# 03_-_28_PINS_SCHEMATIC.net
KiCad netlist of a schematic drawn in Altium Designer
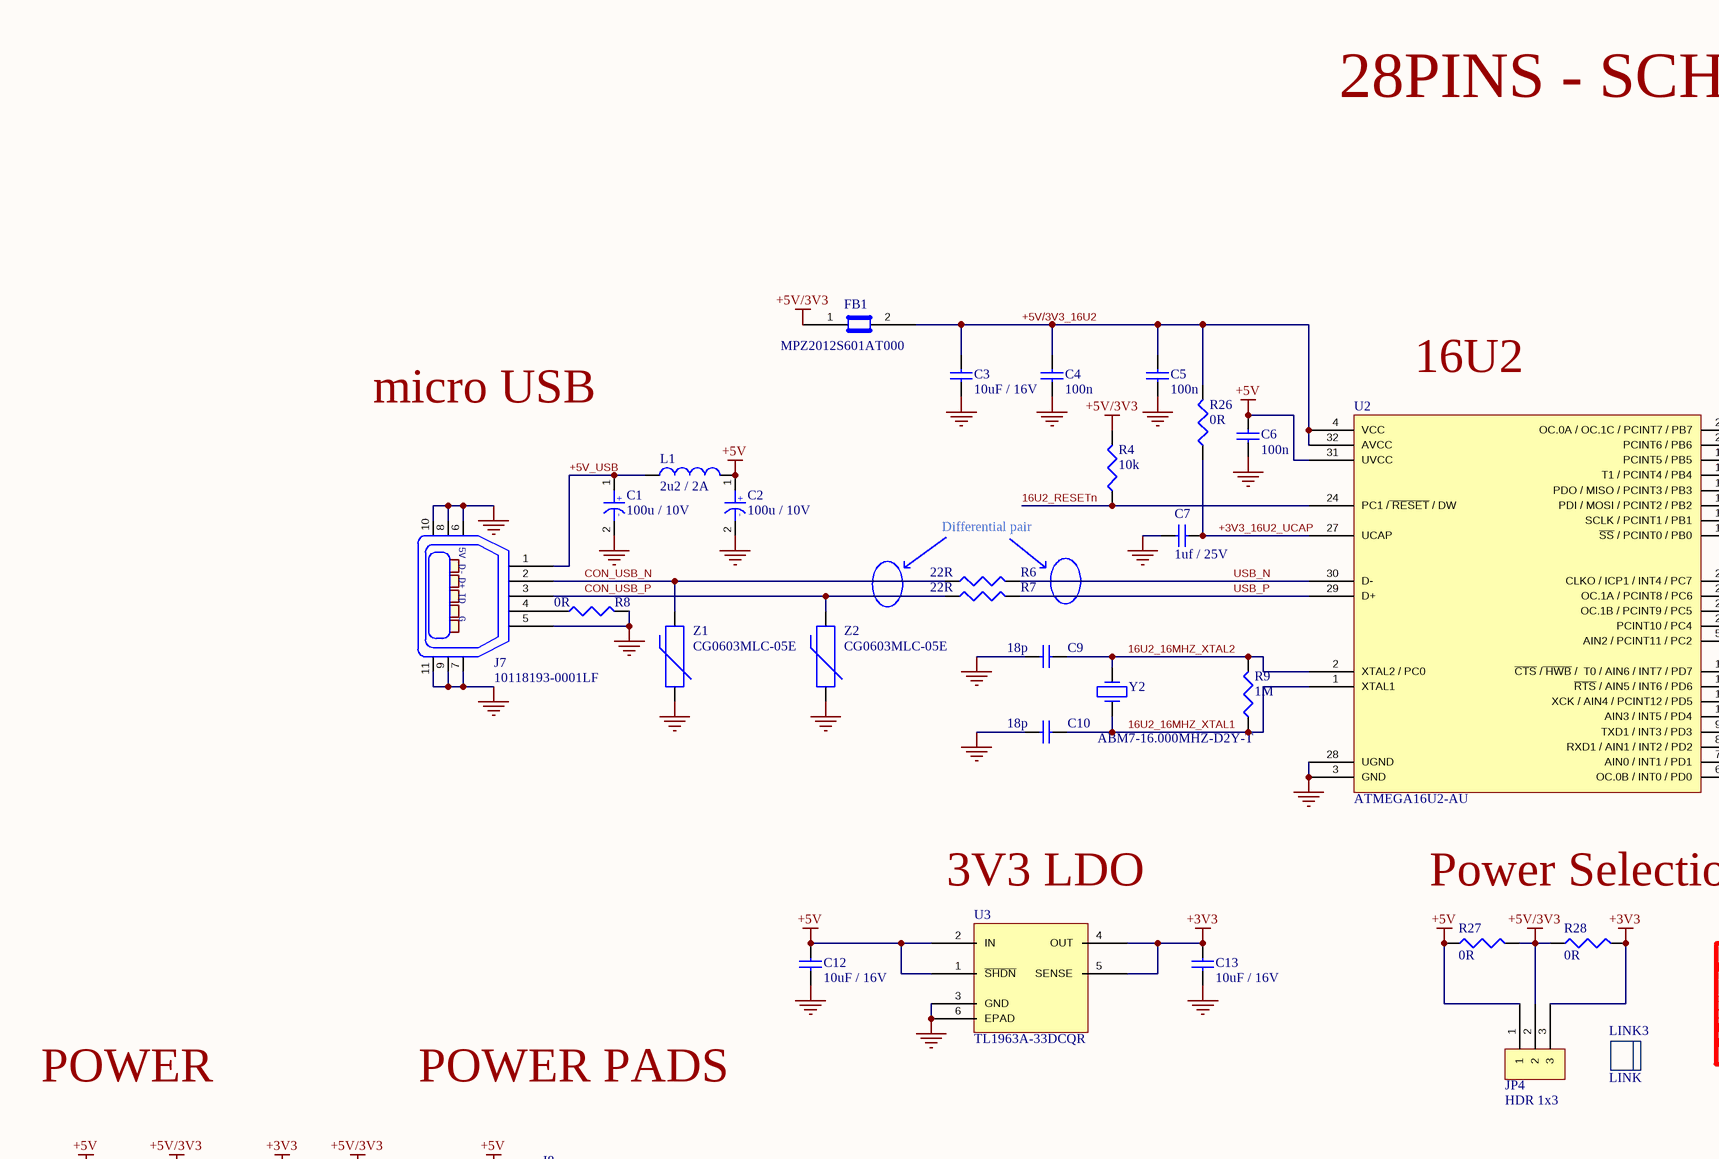
[diagram p0: [03] - 28 PINS SCHEMATIC.SchDoc, top left]
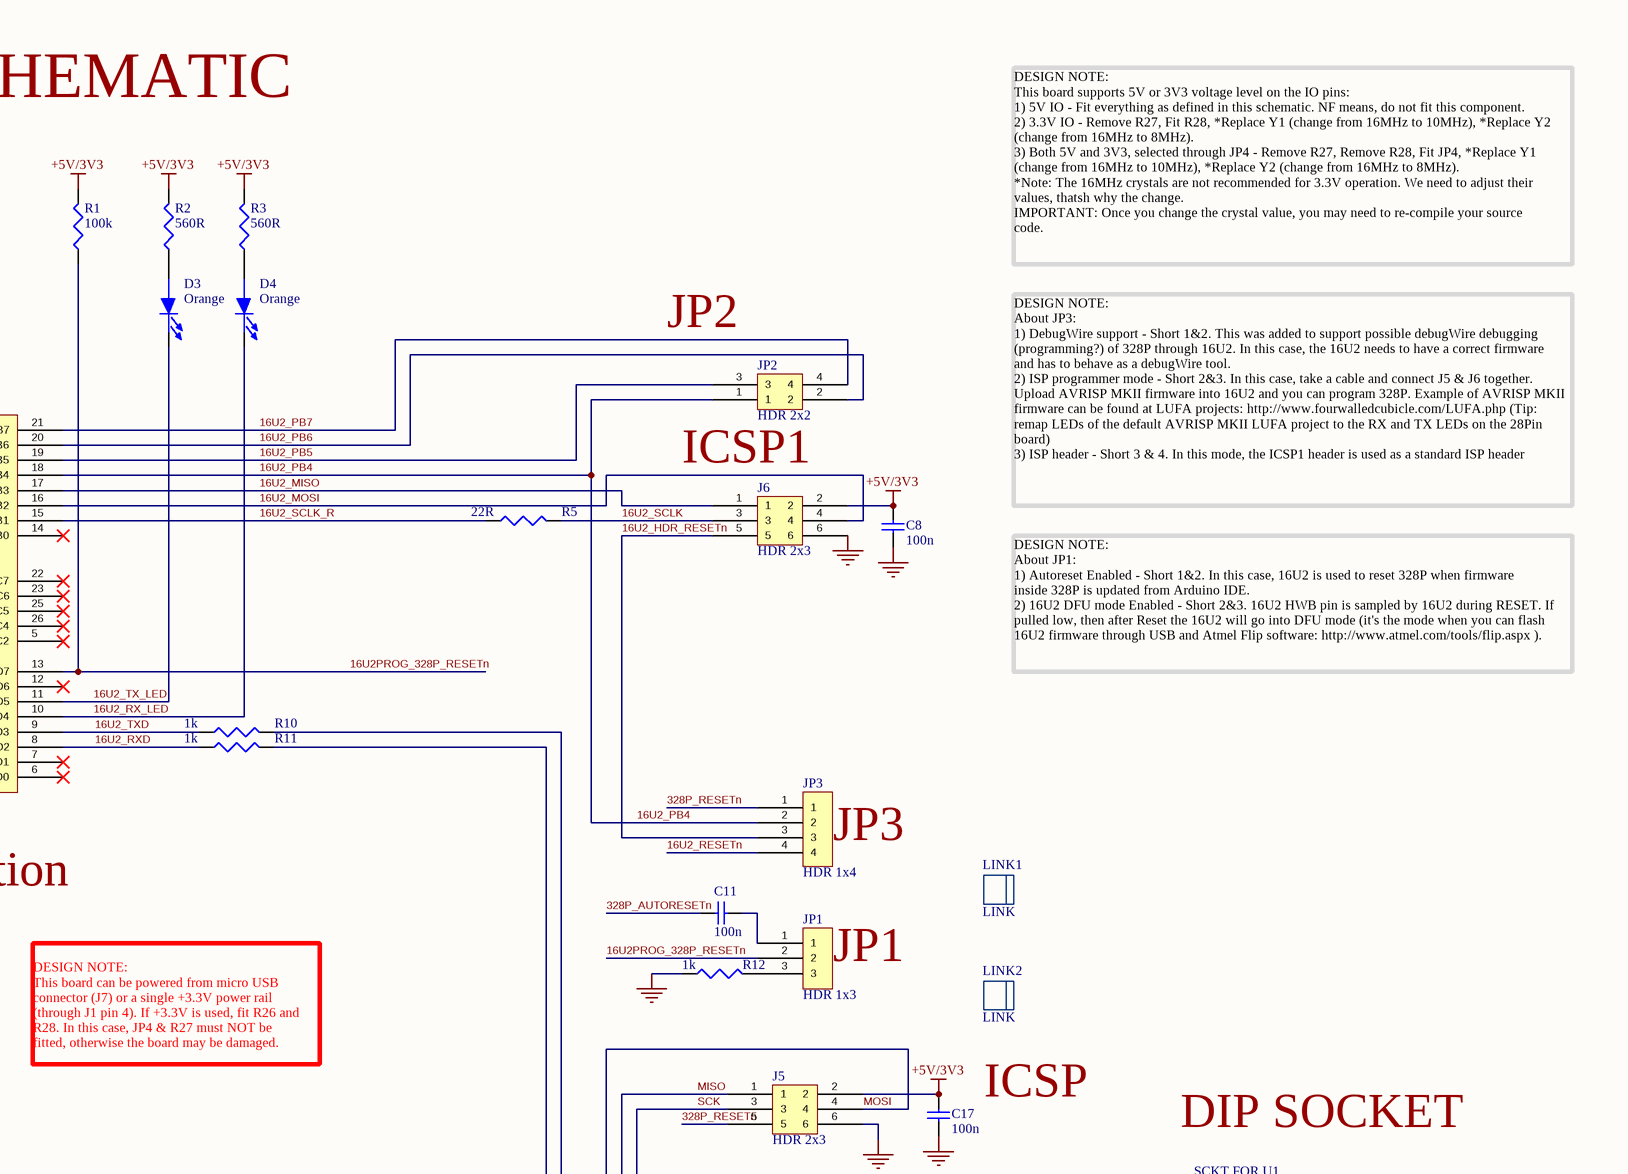
[diagram p1: [03] - 28 PINS SCHEMATIC.SchDoc, top right]
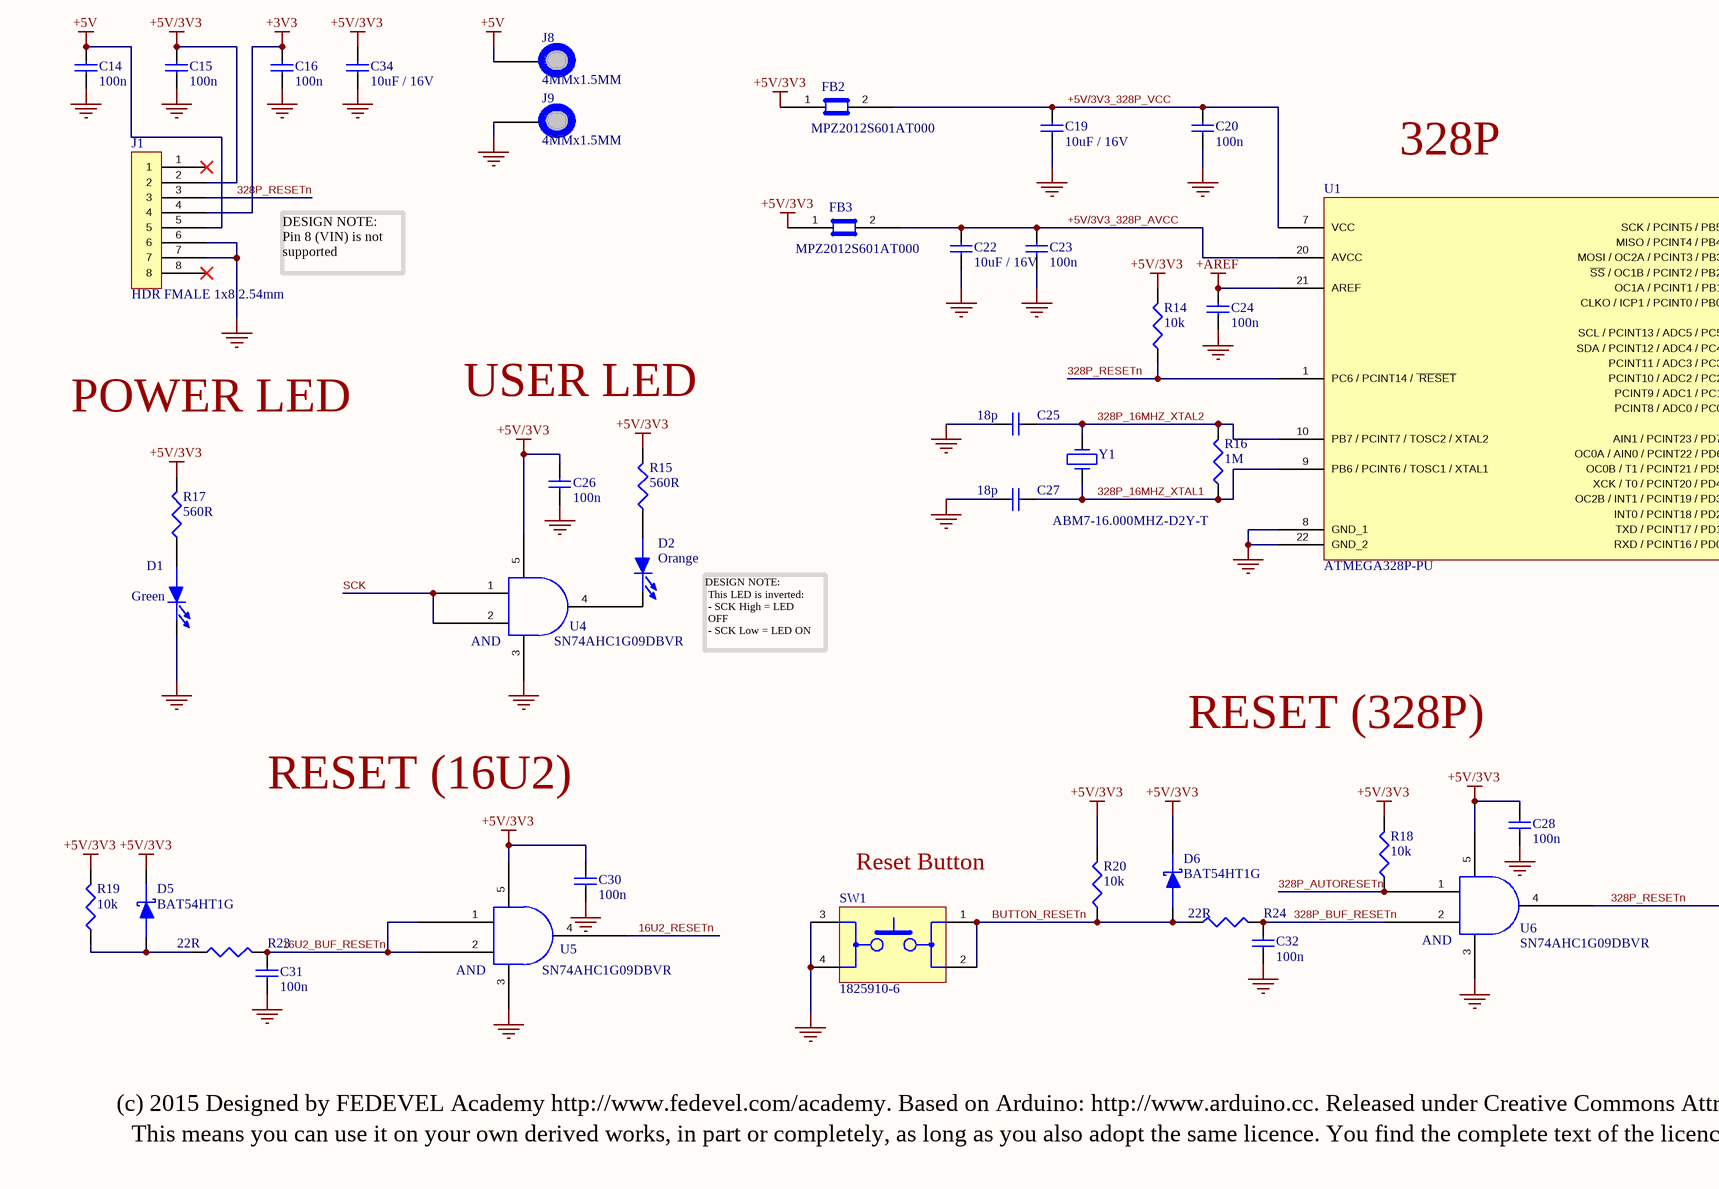
[diagram p2: [03] - 28 PINS SCHEMATIC.SchDoc, bottom left]
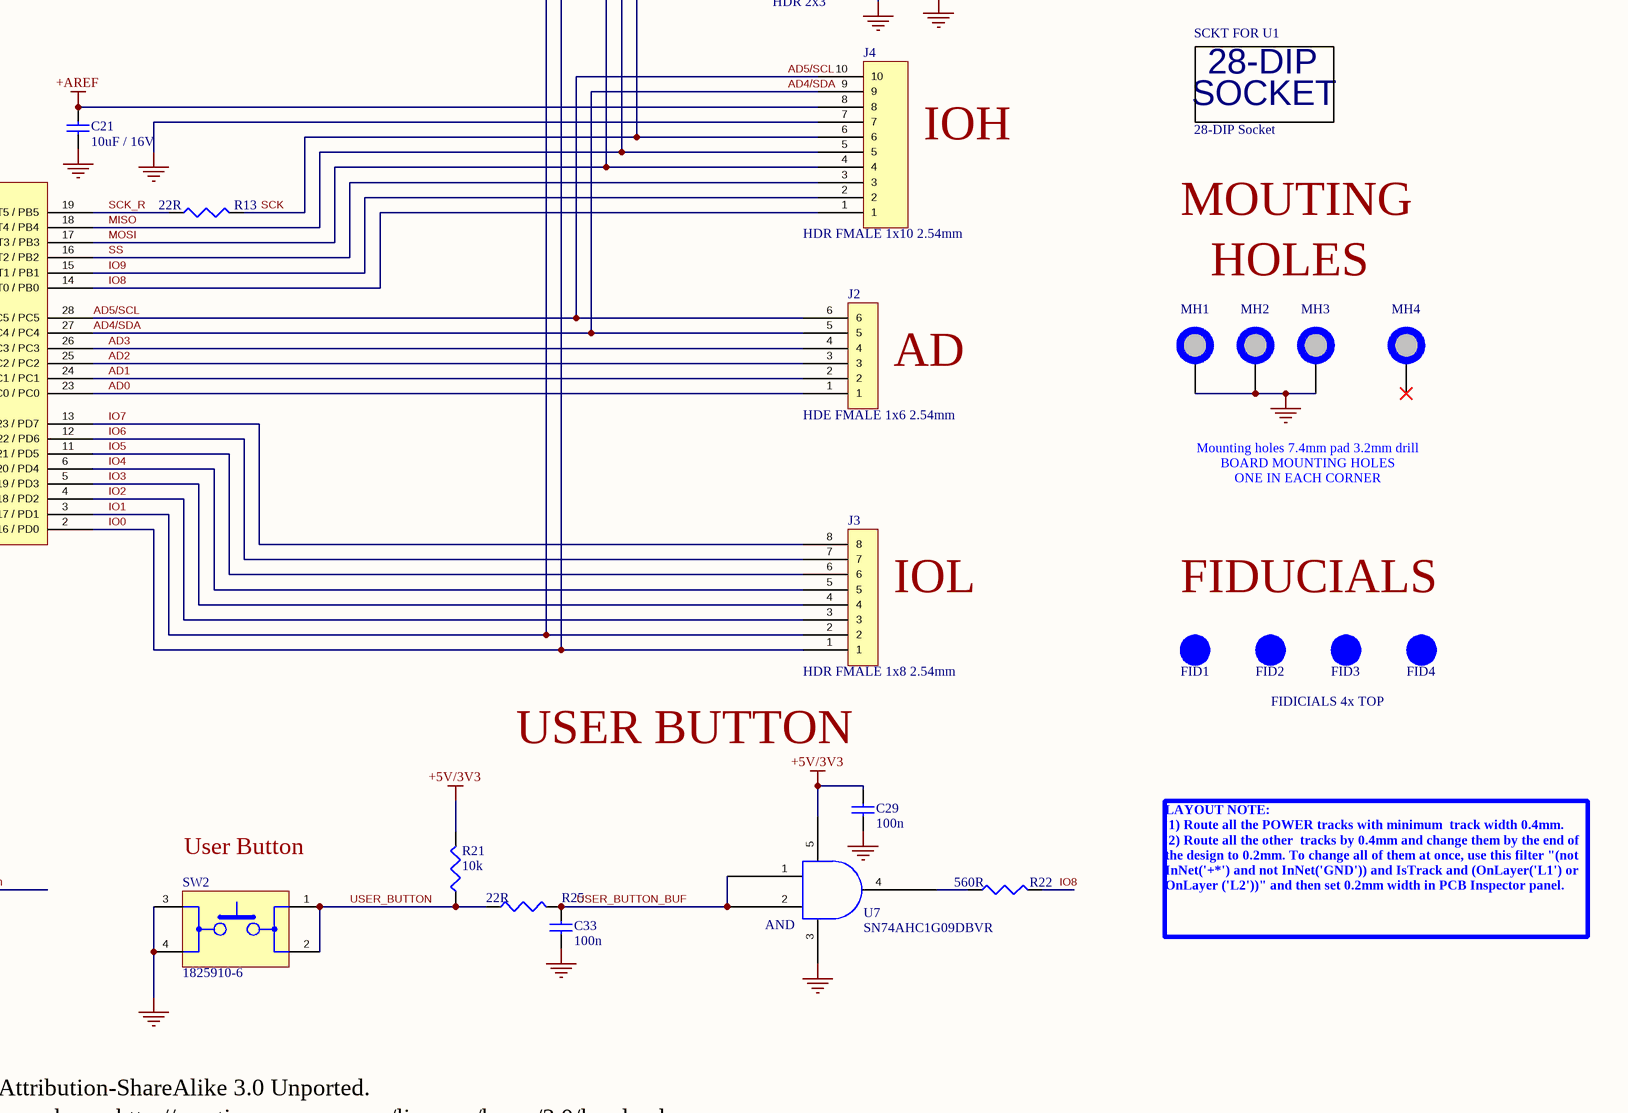
[diagram p3: [03] - 28 PINS SCHEMATIC.SchDoc, bottom right]

(export (version "E")
  (design (tool "Eeschema 10.0.6"))
  (components
    (comp (ref "C1")
      (value "100u / 10V")
      (footprint "C_ALU_C_SIZE")
      (description "Cap Aluminum Lytic 100uF 10V 20% (5 X 5.4mm) SMD 50mA 1000h 85C Automotive T/R")
      (fields
        (field (name "MANUFACTURER") "Panasonic")
        (field (name "MANUFACTURER PART NUMBER") "EEE-1AA101WR")
      )
      (libsource (lib "28Pins_Project_V1I1") (part "EEE-1AA101WR"))
    )
    (comp (ref "C2")
      (value "100u / 10V")
      (footprint "C_ALU_C_SIZE")
      (description "Cap Aluminum Lytic 100uF 10V 20% (5 X 5.4mm) SMD 50mA 1000h 85C Automotive T/R")
      (fields
        (field (name "MANUFACTURER") "Panasonic")
        (field (name "MANUFACTURER PART NUMBER") "EEE-1AA101WR")
      )
      (libsource (lib "28Pins_Project_V1I1") (part "EEE-1AA101WR"))
    )
    (comp (ref "C3")
      (value "10uF / 16V")
      (footprint "C0805 - 10uf")
      (description "CAP CER 10UF 16V X5R 0805")
      (fields
        (field (name "MANUFACTURER") "TDK")
        (field (name "MANUFACTURER PART NUMBER") "C2012X5R1C106M125AC")
      )
      (libsource (lib "28Pins_Project_V1I1") (part "C2012X5R1C106M125AC"))
    )
    (comp (ref "C4")
      (value "100n")
      (footprint "C0805")
      (description "CAP CER 0.1UF 50V X7R 0805")
      (fields
        (field (name "MANUFACTURER") "TDK")
        (field (name "MANUFACTURER PART NUMBER") "C2012X7R1H104K085AA")
      )
      (libsource (lib "28Pins_Project_V1I1") (part "C2012X7R1H104K085AA"))
    )
    (comp (ref "C5")
      (value "100n")
      (footprint "C0805")
      (description "CAP CER 0.1UF 50V X7R 0805")
      (fields
        (field (name "MANUFACTURER") "TDK")
        (field (name "MANUFACTURER PART NUMBER") "C2012X7R1H104K085AA")
      )
      (libsource (lib "28Pins_Project_V1I1") (part "C2012X7R1H104K085AA"))
    )
    (comp (ref "C6")
      (value "100n")
      (footprint "C0805")
      (description "CAP CER 0.1UF 50V X7R 0805")
      (fields
        (field (name "MANUFACTURER") "TDK")
        (field (name "MANUFACTURER PART NUMBER") "C2012X7R1H104K085AA")
      )
      (libsource (lib "28Pins_Project_V1I1") (part "C2012X7R1H104K085AA"))
    )
    (comp (ref "C7")
      (value "1uf / 25V")
      (footprint "C0805")
      (description "CAP CER 1UF 25V X5R 0805")
      (fields
        (field (name "MANUFACTURER") "TDK")
        (field (name "MANUFACTURER PART NUMBER") "C2012X5R1E105K125AA")
      )
      (libsource (lib "28Pins_Project_V1I1") (part "C2012X5R1E105K125AA"))
    )
    (comp (ref "C8")
      (value "100n")
      (footprint "C0805")
      (description "CAP CER 0.1UF 50V X7R 0805")
      (fields
        (field (name "MANUFACTURER") "TDK")
        (field (name "MANUFACTURER PART NUMBER") "C2012X7R1H104K085AA")
      )
      (libsource (lib "28Pins_Project_V1I1") (part "C2012X7R1H104K085AA"))
    )
    (comp (ref "C9")
      (value "18p")
      (footprint "C0805")
      (description "CAP CER 18PF 50V NP0 0805")
      (fields
        (field (name "MANUFACTURER") "KEMET")
        (field (name "MANUFACTURER PART NUMBER") "C0805C180J5GAC-TU")
      )
      (libsource (lib "28Pins_Project_V1I1") (part "C0805C180J5GAC-TU"))
    )
    (comp (ref "C10")
      (value "18p")
      (footprint "C0805")
      (description "CAP CER 18PF 50V NP0 0805")
      (fields
        (field (name "MANUFACTURER") "KEMET")
        (field (name "MANUFACTURER PART NUMBER") "C0805C180J5GAC-TU")
      )
      (libsource (lib "28Pins_Project_V1I1") (part "C0805C180J5GAC-TU"))
    )
    (comp (ref "C11")
      (value "100n")
      (footprint "C0805")
      (description "CAP CER 0.1UF 50V X7R 0805")
      (fields
        (field (name "MANUFACTURER") "TDK")
        (field (name "MANUFACTURER PART NUMBER") "C2012X7R1H104K085AA")
      )
      (libsource (lib "28Pins_Project_V1I1") (part "C2012X7R1H104K085AA"))
    )
    (comp (ref "C12")
      (value "10uF / 16V")
      (footprint "C0805 - 10uf")
      (description "CAP CER 10UF 16V X5R 0805")
      (fields
        (field (name "MANUFACTURER") "TDK")
        (field (name "MANUFACTURER PART NUMBER") "C2012X5R1C106M125AC")
      )
      (libsource (lib "28Pins_Project_V1I1") (part "C2012X5R1C106M125AC"))
    )
    (comp (ref "C13")
      (value "10uF / 16V")
      (footprint "C0805 - 10uf")
      (description "CAP CER 10UF 16V X5R 0805")
      (fields
        (field (name "MANUFACTURER") "TDK")
        (field (name "MANUFACTURER PART NUMBER") "C2012X5R1C106M125AC")
      )
      (libsource (lib "28Pins_Project_V1I1") (part "C2012X5R1C106M125AC"))
    )
    (comp (ref "C14")
      (value "100n")
      (footprint "C0805")
      (description "CAP CER 0.1UF 50V X7R 0805")
      (fields
        (field (name "MANUFACTURER") "TDK")
        (field (name "MANUFACTURER PART NUMBER") "C2012X7R1H104K085AA")
      )
      (libsource (lib "28Pins_Project_V1I1") (part "C2012X7R1H104K085AA"))
    )
    (comp (ref "C15")
      (value "100n")
      (footprint "C0805")
      (description "CAP CER 0.1UF 50V X7R 0805")
      (fields
        (field (name "MANUFACTURER") "TDK")
        (field (name "MANUFACTURER PART NUMBER") "C2012X7R1H104K085AA")
      )
      (libsource (lib "28Pins_Project_V1I1") (part "C2012X7R1H104K085AA"))
    )
    (comp (ref "C16")
      (value "100n")
      (footprint "C0805")
      (description "CAP CER 0.1UF 50V X7R 0805")
      (fields
        (field (name "MANUFACTURER") "TDK")
        (field (name "MANUFACTURER PART NUMBER") "C2012X7R1H104K085AA")
      )
      (libsource (lib "28Pins_Project_V1I1") (part "C2012X7R1H104K085AA"))
    )
    (comp (ref "C17")
      (value "100n")
      (footprint "C0805")
      (description "CAP CER 0.1UF 50V X7R 0805")
      (fields
        (field (name "MANUFACTURER") "TDK")
        (field (name "MANUFACTURER PART NUMBER") "C2012X7R1H104K085AA")
      )
      (libsource (lib "28Pins_Project_V1I1") (part "C2012X7R1H104K085AA"))
    )
    (comp (ref "C19")
      (value "10uF / 16V")
      (footprint "C0805 - 10uf")
      (description "CAP CER 10UF 16V X5R 0805")
      (fields
        (field (name "MANUFACTURER") "TDK")
        (field (name "MANUFACTURER PART NUMBER") "C2012X5R1C106M125AC")
      )
      (libsource (lib "28Pins_Project_V1I1") (part "C2012X5R1C106M125AC"))
    )
    (comp (ref "C20")
      (value "100n")
      (footprint "C0805")
      (description "CAP CER 0.1UF 50V X7R 0805")
      (fields
        (field (name "MANUFACTURER") "TDK")
        (field (name "MANUFACTURER PART NUMBER") "C2012X7R1H104K085AA")
      )
      (libsource (lib "28Pins_Project_V1I1") (part "C2012X7R1H104K085AA"))
    )
    (comp (ref "C21")
      (value "10uF / 16V")
      (footprint "C0805 - 10uf")
      (description "CAP CER 10UF 16V X5R 0805")
      (fields
        (field (name "MANUFACTURER") "TDK")
        (field (name "MANUFACTURER PART NUMBER") "C2012X5R1C106M125AC")
      )
      (libsource (lib "28Pins_Project_V1I1") (part "C2012X5R1C106M125AC"))
    )
    (comp (ref "C22")
      (value "10uF / 16V")
      (footprint "C0805 - 10uf")
      (description "CAP CER 10UF 16V X5R 0805")
      (fields
        (field (name "MANUFACTURER") "TDK")
        (field (name "MANUFACTURER PART NUMBER") "C2012X5R1C106M125AC")
      )
      (libsource (lib "28Pins_Project_V1I1") (part "C2012X5R1C106M125AC"))
    )
    (comp (ref "C23")
      (value "100n")
      (footprint "C0805")
      (description "CAP CER 0.1UF 50V X7R 0805")
      (fields
        (field (name "MANUFACTURER") "TDK")
        (field (name "MANUFACTURER PART NUMBER") "C2012X7R1H104K085AA")
      )
      (libsource (lib "28Pins_Project_V1I1") (part "C2012X7R1H104K085AA"))
    )
    (comp (ref "C24")
      (value "100n")
      (footprint "C0805")
      (description "CAP CER 0.1UF 50V X7R 0805")
      (fields
        (field (name "MANUFACTURER") "TDK")
        (field (name "MANUFACTURER PART NUMBER") "C2012X7R1H104K085AA")
      )
      (libsource (lib "28Pins_Project_V1I1") (part "C2012X7R1H104K085AA"))
    )
    (comp (ref "C25")
      (value "18p")
      (footprint "C0805")
      (description "CAP CER 18PF 50V NP0 0805")
      (fields
        (field (name "MANUFACTURER") "KEMET")
        (field (name "MANUFACTURER PART NUMBER") "C0805C180J5GAC-TU")
      )
      (libsource (lib "28Pins_Project_V1I1") (part "C0805C180J5GAC-TU"))
    )
    (comp (ref "C26")
      (value "100n")
      (footprint "C0805")
      (description "CAP CER 0.1UF 50V X7R 0805")
      (fields
        (field (name "MANUFACTURER") "TDK")
        (field (name "MANUFACTURER PART NUMBER") "C2012X7R1H104K085AA")
      )
      (libsource (lib "28Pins_Project_V1I1") (part "C2012X7R1H104K085AA"))
    )
    (comp (ref "C27")
      (value "18p")
      (footprint "C0805")
      (description "CAP CER 18PF 50V NP0 0805")
      (fields
        (field (name "MANUFACTURER") "KEMET")
        (field (name "MANUFACTURER PART NUMBER") "C0805C180J5GAC-TU")
      )
      (libsource (lib "28Pins_Project_V1I1") (part "C0805C180J5GAC-TU"))
    )
    (comp (ref "C28")
      (value "100n")
      (footprint "C0805")
      (description "CAP CER 0.1UF 50V X7R 0805")
      (fields
        (field (name "MANUFACTURER") "TDK")
        (field (name "MANUFACTURER PART NUMBER") "C2012X7R1H104K085AA")
      )
      (libsource (lib "28Pins_Project_V1I1") (part "C2012X7R1H104K085AA"))
    )
    (comp (ref "C29")
      (value "100n")
      (footprint "C0805")
      (description "CAP CER 0.1UF 50V X7R 0805")
      (fields
        (field (name "MANUFACTURER") "TDK")
        (field (name "MANUFACTURER PART NUMBER") "C2012X7R1H104K085AA")
      )
      (libsource (lib "28Pins_Project_V1I1") (part "C2012X7R1H104K085AA"))
    )
    (comp (ref "C30")
      (value "100n")
      (footprint "C0805")
      (description "CAP CER 0.1UF 50V X7R 0805")
      (fields
        (field (name "MANUFACTURER") "TDK")
        (field (name "MANUFACTURER PART NUMBER") "C2012X7R1H104K085AA")
      )
      (libsource (lib "28Pins_Project_V1I1") (part "C2012X7R1H104K085AA"))
    )
    (comp (ref "C31")
      (value "100n")
      (footprint "C0805")
      (description "CAP CER 0.1UF 50V X7R 0805")
      (fields
        (field (name "MANUFACTURER") "TDK")
        (field (name "MANUFACTURER PART NUMBER") "C2012X7R1H104K085AA")
      )
      (libsource (lib "28Pins_Project_V1I1") (part "C2012X7R1H104K085AA"))
    )
    (comp (ref "C32")
      (value "100n")
      (footprint "C0805")
      (description "CAP CER 0.1UF 50V X7R 0805")
      (fields
        (field (name "MANUFACTURER") "TDK")
        (field (name "MANUFACTURER PART NUMBER") "C2012X7R1H104K085AA")
      )
      (libsource (lib "28Pins_Project_V1I1") (part "C2012X7R1H104K085AA"))
    )
    (comp (ref "C33")
      (value "100n")
      (footprint "C0805")
      (description "CAP CER 0.1UF 50V X7R 0805")
      (fields
        (field (name "MANUFACTURER") "TDK")
        (field (name "MANUFACTURER PART NUMBER") "C2012X7R1H104K085AA")
      )
      (libsource (lib "28Pins_Project_V1I1") (part "C2012X7R1H104K085AA"))
    )
    (comp (ref "C34")
      (value "10uF / 16V")
      (footprint "C0805 - 10uf")
      (description "CAP CER 10UF 16V X5R 0805")
      (fields
        (field (name "MANUFACTURER") "TDK")
        (field (name "MANUFACTURER PART NUMBER") "C2012X5R1C106M125AC")
      )
      (libsource (lib "28Pins_Project_V1I1") (part "C2012X5R1C106M125AC"))
    )
    (comp (ref "D1")
      (value "Green")
      (footprint "LED_0603")
      (description "LED GREEN DIFFUSED 0603 SMD")
      (fields
        (field (name "MANUFACTURER") "Osram Opto")
        (field (name "MANUFACTURER PART NUMBER") "LGL29K-G2J1-24-Z")
      )
      (libsource (lib "28Pins_Project_V1I1") (part "LGL29K-G2J1-24-Z"))
    )
    (comp (ref "D2")
      (value "Orange")
      (footprint "LED_0603")
      (description "LED ORANGE DIFFUSED 0603 SMD")
      (fields
        (field (name "MANUFACTURER") "Osram Opto")
        (field (name "MANUFACTURER PART NUMBER") "LOL29K-H2K1-24-Z")
      )
      (libsource (lib "28Pins_Project_V1I1") (part "LOL29K-H2K1-24-Z"))
    )
    (comp (ref "D3")
      (value "Orange")
      (footprint "LED_0603")
      (description "LED ORANGE DIFFUSED 0603 SMD")
      (fields
        (field (name "MANUFACTURER") "Osram Opto")
        (field (name "MANUFACTURER PART NUMBER") "LOL29K-H2K1-24-Z")
      )
      (libsource (lib "28Pins_Project_V1I1") (part "LOL29K-H2K1-24-Z"))
    )
    (comp (ref "D4")
      (value "Orange")
      (footprint "LED_0603")
      (description "LED ORANGE DIFFUSED 0603 SMD")
      (fields
        (field (name "MANUFACTURER") "Osram Opto")
        (field (name "MANUFACTURER PART NUMBER") "LOL29K-H2K1-24-Z")
      )
      (libsource (lib "28Pins_Project_V1I1") (part "LOL29K-H2K1-24-Z"))
    )
    (comp (ref "D5")
      (value "BAT54HT1G")
      (footprint "SOD323")
      (description "DIODE SCHOTTKY 30V 200MA SOD323")
      (fields (field (name "MANUFACTURER") "ON Semiconductor / Fairchild"))
      (libsource (lib "28Pins_Project_V1I1") (part "BAT54HT1G"))
    )
    (comp (ref "D6")
      (value "BAT54HT1G")
      (footprint "SOD323")
      (description "DIODE SCHOTTKY 30V 200MA SOD323")
      (fields (field (name "MANUFACTURER") "ON Semiconductor / Fairchild"))
      (libsource (lib "28Pins_Project_V1I1") (part "BAT54HT1G"))
    )
    (comp (ref "FB1")
      (value "MPZ2012S601AT000")
      (footprint "C0805")
      (description "TDK   MPZ2012S601AT000   FERRITE BEAD, 0.1OHM, 2A, 0805, FULL REEL")
      (fields (field (name "MANUFACTURER") "TDK"))
      (libsource (lib "28Pins_Project_V1I1") (part "MPZ2012S601AT000"))
    )
    (comp (ref "FB2")
      (value "MPZ2012S601AT000")
      (footprint "C0805")
      (description "TDK   MPZ2012S601AT000   FERRITE BEAD, 0.1OHM, 2A, 0805, FULL REEL")
      (fields (field (name "MANUFACTURER") "TDK"))
      (libsource (lib "28Pins_Project_V1I1") (part "MPZ2012S601AT000"))
    )
    (comp (ref "FB3")
      (value "MPZ2012S601AT000")
      (footprint "C0805")
      (description "TDK   MPZ2012S601AT000   FERRITE BEAD, 0.1OHM, 2A, 0805, FULL REEL")
      (fields (field (name "MANUFACTURER") "TDK"))
      (libsource (lib "28Pins_Project_V1I1") (part "MPZ2012S601AT000"))
    )
    (comp (ref "FID1")
      (value "FID_1MMC")
      (footprint "FID_40x120D")
      (description "Fiducial 40mil Diameter, 20mil Mask")
      (libsource (lib "28Pins_Project_V1I1") (part "FID_1MMC"))
    )
    (comp (ref "FID2")
      (value "FID_1MMC")
      (footprint "FID_40x120D")
      (description "Fiducial 40mil Diameter, 20mil Mask")
      (libsource (lib "28Pins_Project_V1I1") (part "FID_1MMC"))
    )
    (comp (ref "FID3")
      (value "FID_1MMC")
      (footprint "FID_40x120D")
      (description "Fiducial 40mil Diameter, 20mil Mask")
      (libsource (lib "28Pins_Project_V1I1") (part "FID_1MMC"))
    )
    (comp (ref "FID4")
      (value "FID_1MMC")
      (footprint "FID_40x120D")
      (description "Fiducial 40mil Diameter, 20mil Mask")
      (libsource (lib "28Pins_Project_V1I1") (part "FID_1MMC"))
    )
    (comp (ref "J1")
      (value "HDR FMALE 1x8 2.54mm")
      (footprint "HDR FMALE 1x8 2.54mm")
      (description "Headers & Wire Housings 8 PIN SIL VERTICAL SOCKET GOLD+TIN")
      (fields (field (name "MANUFACTURER") "Harwin") (field (name "MANUFACTURER PART NUMBER") "M20-7820842"))
      (libsource (lib "") (part "M20-7820842_1"))
    )
    (comp (ref "J2")
      (value "HDE FMALE 1x6 2.54mm")
      (footprint "HDR FMALE 1x6 2.54mm")
      (description "Headers & Wire Housings 6 PIN SIL VERTICAL SOCKET TIN")
      (fields (field (name "MANUFACTURER") "Harwin") (field (name "MANUFACTURER PART NUMBER") "M20-7820646"))
      (libsource (lib "28Pins_Project_V1I1") (part "M20-7820646"))
    )
    (comp (ref "J3")
      (value "HDR FMALE 1x8 2.54mm")
      (footprint "HDR FMALE 1x8 2.54mm")
      (description "Headers & Wire Housings 8 PIN SIL VERTICAL SOCKET GOLD+TIN")
      (fields (field (name "MANUFACTURER") "Harwin") (field (name "MANUFACTURER PART NUMBER") "M20-7820842"))
      (libsource (lib "28Pins_Project_V1I1") (part "M20-7820842"))
    )
    (comp (ref "J4")
      (value "HDR FMALE 1x10 2.54mm")
      (footprint "HDR FMALE 1x10 2.54mm")
      (description "Headers & Wire Housings 10 PIN SIL VERTICAL SOCKET TIN")
      (fields (field (name "MANUFACTURER") "Harwin") (field (name "MANUFACTURER PART NUMBER") "M20-7821046"))
      (libsource (lib "28Pins_Project_V1I1") (part "M20-7821046"))
    )
    (comp (ref "J5")
      (value "HDR 2x3")
      (footprint "HDR_2x3_2.54mm")
      (description "6 Positions Header, Unshrouded Connector 0.100\" (2.54mm) Through Hole Gold or Gold, GXT™")
      (fields
        (field (name "MANUFACTURER") "Amphenol FCI")
        (field (name "MANUFACTURER PART NUMBER") "67997-106HLF")
      )
      (libsource (lib "28Pins_Project_V1I1") (part "67997-106HLF"))
    )
    (comp (ref "J6")
      (value "HDR 2x3")
      (footprint "HDR_2x3_2.54mm")
      (description "6 Positions Header, Unshrouded Connector 0.100\" (2.54mm) Through Hole Gold or Gold, GXT™")
      (fields
        (field (name "MANUFACTURER") "Amphenol FCI")
        (field (name "MANUFACTURER PART NUMBER") "67997-106HLF")
      )
      (libsource (lib "28Pins_Project_V1I1") (part "67997-106HLF"))
    )
    (comp (ref "J7")
      (value "10118193-0001LF")
      (footprint "10118193")
      (description "USB - micro B USB 2.0 Receptacle Connector 5 Position Surface Mount, Right Angle, Horizontal")
      (fields (field (name "MANUFACTURER") "Amphenol FCI"))
      (libsource (lib "28Pins_Project_V1I1") (part "10118193-0001LF"))
    )
    (comp (ref "J8")
      (value "4MMx1.5MM")
      (footprint "PAD_WITH_HOLE_4MMx1.5MM")
      (description "Pad with a hole 4mmx1.5mm")
      (libsource (lib "28Pins_Project_V1I1") (part "PAD_WITH_HOLE_4MMx1.5MM"))
    )
    (comp (ref "J9")
      (value "4MMx1.5MM")
      (footprint "PAD_WITH_HOLE_4MMx1.5MM")
      (description "Pad with a hole 4mmx1.5mm")
      (libsource (lib "28Pins_Project_V1I1") (part "PAD_WITH_HOLE_4MMx1.5MM"))
    )
    (comp (ref "JP1")
      (value "HDR 1x3")
      (footprint "HDR FMALE 1x3 2.54mm")
      (description "3 Positions Header, Unshrouded Connector 0.100\" (2.54mm) Through Hole Gold or Gold, GXT™")
      (fields
        (field (name "MANUFACTURER") "Amphenol FCI")
        (field (name "MANUFACTURER PART NUMBER") "68000-103HLF")
      )
      (libsource (lib "") (part "68000-103HLF_1"))
    )
    (comp (ref "JP2")
      (value "HDR 2x2")
      (footprint "HDR_2x2_2.54mm")
      (description "4 Positions Header, Unshrouded Connector 0.100\" (2.54mm) Through Hole Gold or Gold, GXT™")
      (fields
        (field (name "MANUFACTURER") "Amphenol FCI")
        (field (name "MANUFACTURER PART NUMBER") "68602-204HLF")
      )
      (libsource (lib "28Pins_Project_V1I1") (part "68602-204HLF"))
    )
    (comp (ref "JP3")
      (value "HDR 1x4")
      (footprint "HDR _1x4_2.54mm")
      (description "4 Positions Header, Unshrouded Connector 0.100\" (2.54mm) Through Hole Gold or Gold, GXT™")
      (fields
        (field (name "MANUFACTURER") "Amphenol FCI")
        (field (name "MANUFACTURER PART NUMBER") "68001-204HLF")
      )
      (libsource (lib "28Pins_Project_V1I1") (part "68001-204HLF"))
    )
    (comp (ref "JP4")
      (value "HDR 1x3")
      (footprint "HDR FMALE 1x3 2.54mm")
      (description "3 Positions Header, Unshrouded Connector 0.100\" (2.54mm) Through Hole Gold or Gold, GXT™")
      (fields
        (field (name "MANUFACTURER") "Amphenol FCI")
        (field (name "MANUFACTURER PART NUMBER") "68000-103HLF")
      )
      (libsource (lib "28Pins_Project_V1I1") (part "68000-103HLF"))
    )
    (comp (ref "L1")
      (value "2u2 / 2A")
      (footprint "C1210_IND")
      (description "Inductor Chip Wirewound 2.2uH 20% 100KHz 1.13A 80mOhm DCR 1210 T/R")
      (fields
        (field (name "MANUFACTURER") "KEMET")
        (field (name "MANUFACTURER PART NUMBER") "L1210R2R2MDWIT")
      )
      (libsource (lib "28Pins_Project_V1I1") (part "L1210R2R2MDWIT"))
    )
    (comp (ref "LINK1")
      (value "LINK")
      (description "CONN JUMPER SHORTING .100\" GOLD")
      (fields
        (field (name "MANUFACTURER") "Sullins")
        (field (name "MANUFACTURER PART NUMBER") "QPC02SXGN-RC")
      )
      (libsource (lib "28Pins_Project_V1I1") (part "QPC02SXGN-RC"))
    )
    (comp (ref "LINK2")
      (value "LINK")
      (description "CONN JUMPER SHORTING .100\" GOLD")
      (fields
        (field (name "MANUFACTURER") "Sullins")
        (field (name "MANUFACTURER PART NUMBER") "QPC02SXGN-RC")
      )
      (libsource (lib "28Pins_Project_V1I1") (part "QPC02SXGN-RC"))
    )
    (comp (ref "LINK3")
      (value "LINK")
      (description "CONN JUMPER SHORTING .100\" GOLD")
      (fields
        (field (name "MANUFACTURER") "Sullins")
        (field (name "MANUFACTURER PART NUMBER") "QPC02SXGN-RC")
      )
      (libsource (lib "28Pins_Project_V1I1") (part "QPC02SXGN-RC"))
    )
    (comp (ref "MH1")
      (value "MH_7.4MMC_3.2MMD")
      (footprint "MH_7.4MMC_3.2MMD")
      (description "Mounting Hole 7.4mm Diameter, 3.2mm Drill")
      (libsource (lib "28Pins_Project_V1I1") (part "MH_7.4MMC_3.2MMD"))
    )
    (comp (ref "MH2")
      (value "MH_7.4MMC_3.2MMD")
      (footprint "MH_7.4MMC_3.2MMD")
      (description "Mounting Hole 7.4mm Diameter, 3.2mm Drill")
      (libsource (lib "28Pins_Project_V1I1") (part "MH_7.4MMC_3.2MMD"))
    )
    (comp (ref "MH3")
      (value "MH_7.4MMC_3.2MMD")
      (footprint "MH_7.4MMC_3.2MMD")
      (description "Mounting Hole 7.4mm Diameter, 3.2mm Drill")
      (libsource (lib "28Pins_Project_V1I1") (part "MH_7.4MMC_3.2MMD"))
    )
    (comp (ref "MH4")
      (value "MH_7.4MMNC_3.2MMD")
      (footprint "MH_7.4MMNC_3.2MMD_NON_COPPER_NPTH")
      (description "Hole 7.4mm Diameter (Non Copper), 3.2mm Drill NPTH")
      (libsource (lib "28Pins_Project_V1I1") (part "MH_7.4MMNC_3.2MMD"))
    )
    (comp (ref "R1")
      (value "100k")
      (footprint "R0805")
      (description "RES SMD 100K OHM 1% 1/8W 0805")
      (fields
        (field (name "MANUFACTURER") "Yageo")
        (field (name "MANUFACTURER PART NUMBER") "RT0805FRE07100KL")
      )
      (libsource (lib "28Pins_Project_V1I1") (part "RT0805FRE07100KL"))
    )
    (comp (ref "R2")
      (value "560R")
      (footprint "R0805")
      (description "RES SMD 560 OHM 1% 1/8W 0805")
      (fields
        (field (name "MANUFACTURER") "Yageo")
        (field (name "MANUFACTURER PART NUMBER") "RC0805FR-07560RL")
      )
      (libsource (lib "28Pins_Project_V1I1") (part "RC0805FR-07560RL"))
    )
    (comp (ref "R3")
      (value "560R")
      (footprint "R0805")
      (description "RES SMD 560 OHM 1% 1/8W 0805")
      (fields
        (field (name "MANUFACTURER") "Yageo")
        (field (name "MANUFACTURER PART NUMBER") "RC0805FR-07560RL")
      )
      (libsource (lib "28Pins_Project_V1I1") (part "RC0805FR-07560RL"))
    )
    (comp (ref "R4")
      (value "10k")
      (footprint "R0805")
      (description "RES SMD 10K OHM 1% 1/8W 0805")
      (fields
        (field (name "MANUFACTURER") "Yageo")
        (field (name "MANUFACTURER PART NUMBER") "RC0805FR-0710KL")
      )
      (libsource (lib "28Pins_Project_V1I1") (part "RC0805FR-0710KL"))
    )
    (comp (ref "R5")
      (value "22R")
      (footprint "R0805")
      (description "RES SMD 22 OHM 1% 1/8W 0805")
      (fields
        (field (name "MANUFACTURER") "Yageo")
        (field (name "MANUFACTURER PART NUMBER") "RC0805FR-0722RL")
      )
      (libsource (lib "28Pins_Project_V1I1") (part "RC0805FR-0722RL"))
    )
    (comp (ref "R6")
      (value "22R")
      (footprint "R0805")
      (description "RES SMD 22 OHM 1% 1/8W 0805")
      (fields
        (field (name "MANUFACTURER") "Yageo")
        (field (name "MANUFACTURER PART NUMBER") "RC0805FR-0722RL")
      )
      (libsource (lib "28Pins_Project_V1I1") (part "RC0805FR-0722RL"))
    )
    (comp (ref "R7")
      (value "22R")
      (footprint "R0805")
      (description "RES SMD 22 OHM 1% 1/8W 0805")
      (fields
        (field (name "MANUFACTURER") "Yageo")
        (field (name "MANUFACTURER PART NUMBER") "RC0805FR-0722RL")
      )
      (libsource (lib "28Pins_Project_V1I1") (part "RC0805FR-0722RL"))
    )
    (comp (ref "R8")
      (value "0R")
      (footprint "R0805")
      (description "YAGEO         RC0805JR-070RL             RES, THICK FILM, 0R, 0.125W, 0805")
      (fields
        (field (name "MANUFACTURER") "Yageo")
        (field (name "MANUFACTURER PART NUMBER") "RC0805JR-070RL")
      )
      (libsource (lib "28Pins_Project_V1I1") (part "RC0805JR-070RL"))
    )
    (comp (ref "R9")
      (value "1M")
      (footprint "R0805")
      (description "Yageo RC0805 Series Thick Film Surface Mount Resistor 0805 Case 1MO ±1% 0.125W ±100ppm/°C")
      (fields
        (field (name "MANUFACTURER") "Yageo Phycomp")
        (field (name "MANUFACTURER PART NUMBER") "RC0805FR-071ML")
      )
      (libsource (lib "28Pins_Project_V1I1") (part "RC0805FR-071ML"))
    )
    (comp (ref "R10")
      (value "1k")
      (footprint "R0805")
      (description "RES SMD 1K OHM 1% 1/8W 0805")
      (fields
        (field (name "MANUFACTURER") "Yageo")
        (field (name "MANUFACTURER PART NUMBER") "RC0805FR-071KL")
      )
      (libsource (lib "28Pins_Project_V1I1") (part "RC0805FR-071KL"))
    )
    (comp (ref "R11")
      (value "1k")
      (footprint "R0805")
      (description "RES SMD 1K OHM 1% 1/8W 0805")
      (fields
        (field (name "MANUFACTURER") "Yageo")
        (field (name "MANUFACTURER PART NUMBER") "RC0805FR-071KL")
      )
      (libsource (lib "28Pins_Project_V1I1") (part "RC0805FR-071KL"))
    )
    (comp (ref "R12")
      (value "1k")
      (footprint "R0805")
      (description "RES SMD 1K OHM 1% 1/8W 0805")
      (fields
        (field (name "MANUFACTURER") "Yageo")
        (field (name "MANUFACTURER PART NUMBER") "RC0805FR-071KL")
      )
      (libsource (lib "28Pins_Project_V1I1") (part "RC0805FR-071KL"))
    )
    (comp (ref "R13")
      (value "22R")
      (footprint "R0805")
      (description "RES SMD 22 OHM 1% 1/8W 0805")
      (fields
        (field (name "MANUFACTURER") "Yageo")
        (field (name "MANUFACTURER PART NUMBER") "RC0805FR-0722RL")
      )
      (libsource (lib "28Pins_Project_V1I1") (part "RC0805FR-0722RL"))
    )
    (comp (ref "R14")
      (value "10k")
      (footprint "R0805")
      (description "RES SMD 10K OHM 1% 1/8W 0805")
      (fields
        (field (name "MANUFACTURER") "Yageo")
        (field (name "MANUFACTURER PART NUMBER") "RC0805FR-0710KL")
      )
      (libsource (lib "28Pins_Project_V1I1") (part "RC0805FR-0710KL"))
    )
    (comp (ref "R15")
      (value "560R")
      (footprint "R0805")
      (description "RES SMD 560 OHM 1% 1/8W 0805")
      (fields
        (field (name "MANUFACTURER") "Yageo")
        (field (name "MANUFACTURER PART NUMBER") "RC0805FR-07560RL")
      )
      (libsource (lib "28Pins_Project_V1I1") (part "RC0805FR-07560RL"))
    )
    (comp (ref "R16")
      (value "1M")
      (footprint "R0805")
      (description "Yageo RC0805 Series Thick Film Surface Mount Resistor 0805 Case 1MO ±1% 0.125W ±100ppm/°C")
      (fields
        (field (name "MANUFACTURER") "Yageo Phycomp")
        (field (name "MANUFACTURER PART NUMBER") "RC0805FR-071ML")
      )
      (libsource (lib "28Pins_Project_V1I1") (part "RC0805FR-071ML"))
    )
    (comp (ref "R17")
      (value "560R")
      (footprint "R0805")
      (description "RES SMD 560 OHM 1% 1/8W 0805")
      (fields
        (field (name "MANUFACTURER") "Yageo")
        (field (name "MANUFACTURER PART NUMBER") "RC0805FR-07560RL")
      )
      (libsource (lib "28Pins_Project_V1I1") (part "RC0805FR-07560RL"))
    )
    (comp (ref "R18")
      (value "10k")
      (footprint "R0805")
      (description "RES SMD 10K OHM 1% 1/8W 0805")
      (fields
        (field (name "MANUFACTURER") "Yageo")
        (field (name "MANUFACTURER PART NUMBER") "RC0805FR-0710KL")
      )
      (libsource (lib "28Pins_Project_V1I1") (part "RC0805FR-0710KL"))
    )
    (comp (ref "R19")
      (value "10k")
      (footprint "R0805")
      (description "RES SMD 10K OHM 1% 1/8W 0805")
      (fields
        (field (name "MANUFACTURER") "Yageo")
        (field (name "MANUFACTURER PART NUMBER") "RC0805FR-0710KL")
      )
      (libsource (lib "28Pins_Project_V1I1") (part "RC0805FR-0710KL"))
    )
    (comp (ref "R20")
      (value "10k")
      (footprint "R0805")
      (description "RES SMD 10K OHM 1% 1/8W 0805")
      (fields
        (field (name "MANUFACTURER") "Yageo")
        (field (name "MANUFACTURER PART NUMBER") "RC0805FR-0710KL")
      )
      (libsource (lib "28Pins_Project_V1I1") (part "RC0805FR-0710KL"))
    )
    (comp (ref "R21")
      (value "10k")
      (footprint "R0805")
      (description "RES SMD 10K OHM 1% 1/8W 0805")
      (fields
        (field (name "MANUFACTURER") "Yageo")
        (field (name "MANUFACTURER PART NUMBER") "RC0805FR-0710KL")
      )
      (libsource (lib "28Pins_Project_V1I1") (part "RC0805FR-0710KL"))
    )
    (comp (ref "R22")
      (value "560R")
      (footprint "R0805")
      (description "RES SMD 560 OHM 1% 1/8W 0805")
      (fields
        (field (name "MANUFACTURER") "Yageo")
        (field (name "MANUFACTURER PART NUMBER") "RC0805FR-07560RL")
      )
      (libsource (lib "28Pins_Project_V1I1") (part "RC0805FR-07560RL"))
    )
    (comp (ref "R23")
      (value "22R")
      (footprint "R0805")
      (description "RES SMD 22 OHM 1% 1/8W 0805")
      (fields
        (field (name "MANUFACTURER") "Yageo")
        (field (name "MANUFACTURER PART NUMBER") "RC0805FR-0722RL")
      )
      (libsource (lib "28Pins_Project_V1I1") (part "RC0805FR-0722RL"))
    )
    (comp (ref "R24")
      (value "22R")
      (footprint "R0805")
      (description "RES SMD 22 OHM 1% 1/8W 0805")
      (fields
        (field (name "MANUFACTURER") "Yageo")
        (field (name "MANUFACTURER PART NUMBER") "RC0805FR-0722RL")
      )
      (libsource (lib "28Pins_Project_V1I1") (part "RC0805FR-0722RL"))
    )
    (comp (ref "R25")
      (value "22R")
      (footprint "R0805")
      (description "RES SMD 22 OHM 1% 1/8W 0805")
      (fields
        (field (name "MANUFACTURER") "Yageo")
        (field (name "MANUFACTURER PART NUMBER") "RC0805FR-0722RL")
      )
      (libsource (lib "28Pins_Project_V1I1") (part "RC0805FR-0722RL"))
    )
    (comp (ref "R26")
      (value "0R")
      (footprint "R0805")
      (description "YAGEO         RC0805JR-070RL             RES, THICK FILM, 0R, 0.125W, 0805")
      (fields
        (field (name "MANUFACTURER") "Yageo")
        (field (name "MANUFACTURER PART NUMBER") "RC0805JR-070RL")
      )
      (libsource (lib "28Pins_Project_V1I1") (part "RC0805JR-070RL"))
    )
    (comp (ref "R27")
      (value "0R")
      (footprint "R0805")
      (description "YAGEO         RC0805JR-070RL             RES, THICK FILM, 0R, 0.125W, 0805")
      (fields
        (field (name "MANUFACTURER") "Yageo")
        (field (name "MANUFACTURER PART NUMBER") "RC0805JR-070RL")
      )
      (libsource (lib "28Pins_Project_V1I1") (part "RC0805JR-070RL"))
    )
    (comp (ref "R28")
      (value "0R")
      (footprint "R0805")
      (description "YAGEO         RC0805JR-070RL             RES, THICK FILM, 0R, 0.125W, 0805")
      (fields
        (field (name "MANUFACTURER") "Yageo")
        (field (name "MANUFACTURER PART NUMBER") "RC0805JR-070RL")
      )
      (libsource (lib "28Pins_Project_V1I1") (part "RC0805JR-070RL"))
    )
    (comp (ref "SCKT FOR U1")
      (value "28-DIP Socket")
      (footprint "28_DIP_7.62mm_SOCKET")
      (description "SOCKET IC OPEN FRAME 28POS .3\"")
      (fields (field (name "MANUFACTURER") "3M") (field (name "MANUFACTURER PART NUMBER") "4828-3004-CP"))
      (libsource (lib "28Pins_Project_V1I1") (part "4828-3004-CP"))
    )
    (comp (ref "SW1")
      (value "1825910-6")
      (footprint "1825910-6")
      (description "Switch Push Button OFF (ON) SPST Round Button 0.05A 24VDC Momentary Contact PC Pins Thru-Hole")
      (fields (field (name "MANUFACTURER") "TE Connectivity Alcoswitch"))
      (libsource (lib "28Pins_Project_V1I1") (part "1825910-6"))
    )
    (comp (ref "SW2")
      (value "1825910-6")
      (footprint "1825910-6")
      (description "Switch Push Button OFF (ON) SPST Round Button 0.05A 24VDC Momentary Contact PC Pins Thru-Hole")
      (fields (field (name "MANUFACTURER") "TE Connectivity Alcoswitch"))
      (libsource (lib "28Pins_Project_V1I1") (part "1825910-6"))
    )
    (comp (ref "U1")
      (value "ATMEGA328P-PU")
      (footprint "28_DIP_7.62MM")
      (fields (field (name "MANUFACTURER") "Microchip / Atmel"))
      (libsource (lib "28Pins_Project_V1I1") (part "ATMEGA328P-PU"))
    )
    (comp (ref "U2")
      (value "ATMEGA16U2-AU")
      (footprint "TQFP32")
      (description "ATMEL         ATMEGA16U2-AU            MCU, 8BIT, MEGAAVR, 16MHZ, TQFP-32")
      (fields (field (name "MANUFACTURER") "Microchip / Atmel"))
      (libsource (lib "28Pins_Project_V1I1") (part "ATMEGA16U2-AU"))
    )
    (comp (ref "U3")
      (value "TL1963A-33DCQR")
      (footprint "DCQ (R-PDSO-G6)")
      (description "IC REG LDO 3.3V 1.5A SOT223-6")
      (fields (field (name "MANUFACTURER") "Texas Instruments"))
      (libsource (lib "28Pins_Project_V1I1") (part "TL1963A-33DCQR"))
    )
    (comp (ref "U4")
      (value "SN74AHC1G09DBVR")
      (footprint "DBV_SOT_23_5")
      (description "IC GATE AND 1CH 2-INP SOT-23-5")
      (fields (field (name "MANUFACTURER") "Texas Instruments"))
      (libsource (lib "28Pins_Project_V1I1") (part "SN74AHC1G09DBVR"))
    )
    (comp (ref "U5")
      (value "SN74AHC1G09DBVR")
      (footprint "DBV_SOT_23_5")
      (description "IC GATE AND 1CH 2-INP SOT-23-5")
      (fields (field (name "MANUFACTURER") "Texas Instruments"))
      (libsource (lib "28Pins_Project_V1I1") (part "SN74AHC1G09DBVR"))
    )
    (comp (ref "U6")
      (value "SN74AHC1G09DBVR")
      (footprint "DBV_SOT_23_5")
      (description "IC GATE AND 1CH 2-INP SOT-23-5")
      (fields (field (name "MANUFACTURER") "Texas Instruments"))
      (libsource (lib "28Pins_Project_V1I1") (part "SN74AHC1G09DBVR"))
    )
    (comp (ref "U7")
      (value "SN74AHC1G09DBVR")
      (footprint "DBV_SOT_23_5")
      (description "IC GATE AND 1CH 2-INP SOT-23-5")
      (fields (field (name "MANUFACTURER") "Texas Instruments"))
      (libsource (lib "28Pins_Project_V1I1") (part "SN74AHC1G09DBVR"))
    )
    (comp (ref "Y1")
      (value "ABM7-16.000MHZ-D2Y-T")
      (footprint "ABM7_v1_1_BIG")
      (description "Crystals 16.0MHz 20ppm 18pF -40C+85C")
      (fields (field (name "MANUFACTURER") "Abracon") (field (name "TOLERANCE") "20ppm"))
      (libsource (lib "28Pins_Project_V1I1") (part "ABM7-16.000MHZ-D2Y-T"))
    )
    (comp (ref "Y2")
      (value "ABM7-16.000MHZ-D2Y-T")
      (footprint "ABM7_v1_1_BIG")
      (description "Crystals 16.0MHz 20ppm 18pF -40C+85C")
      (fields (field (name "MANUFACTURER") "Abracon") (field (name "TOLERANCE") "20ppm"))
      (libsource (lib "28Pins_Project_V1I1") (part "ABM7-16.000MHZ-D2Y-T"))
    )
    (comp (ref "Z1")
      (value "CG0603MLC-05E")
      (footprint "R0603")
      (fields (field (name "MANUFACTURER") "Bourns") (field (name "VOLTAGE") "5V"))
      (libsource (lib "28Pins_Project_V1I1") (part "CG0603MLC-05E"))
    )
    (comp (ref "Z2")
      (value "CG0603MLC-05E")
      (footprint "R0603")
      (fields (field (name "MANUFACTURER") "Bourns") (field (name "VOLTAGE") "5V"))
      (libsource (lib "28Pins_Project_V1I1") (part "CG0603MLC-05E"))
    )
  )
  (nets
    (net (code "1") (name "+3V3") (class "Default")
      (node (ref "C13") (pin "2") (pinfunction "2_2") (pintype "passive"))
      (node (ref "C16") (pin "2") (pinfunction "2_2") (pintype "passive"))
      (node (ref "J1") (pin "4") (pinfunction "4_4") (pintype "passive"))
      (node (ref "JP4") (pin "3") (pinfunction "3_3") (pintype "passive"))
      (node (ref "R28") (pin "2") (pinfunction "2_2") (pintype "passive"))
      (node (ref "U3") (pin "4") (pinfunction "OUT_4") (pintype "passive"))
      (node (ref "U3") (pin "5") (pinfunction "SENSE_5") (pintype "passive"))
    )
    (net (code "2") (name "+5V") (class "Default")
      (node (ref "C12") (pin "2") (pinfunction "2_2") (pintype "passive"))
      (node (ref "C14") (pin "2") (pinfunction "2_2") (pintype "passive"))
      (node (ref "C2") (pin "1") (pinfunction "1_1") (pintype "passive"))
      (node (ref "C6") (pin "2") (pinfunction "2_2") (pintype "passive"))
      (node (ref "J1") (pin "5") (pinfunction "5_5") (pintype "passive"))
      (node (ref "J8") (pin "1") (pinfunction "1_1") (pintype "passive"))
      (node (ref "JP4") (pin "1") (pinfunction "1_1") (pintype "passive"))
      (node (ref "L1") (pin "2") (pinfunction "2_2") (pintype "passive"))
      (node (ref "R27") (pin "1") (pinfunction "1_1") (pintype "passive"))
      (node (ref "U2") (pin "31") (pinfunction "UVCC_31") (pintype "passive"))
      (node (ref "U3") (pin "1") (pinfunction "~{SHDN}_1") (pintype "passive"))
      (node (ref "U3") (pin "2") (pinfunction "IN_2") (pintype "passive"))
    )
    (net (code "3") (name "+5V{slash}3V3") (class "Default")
      (node (ref "C15") (pin "2") (pinfunction "2_2") (pintype "passive"))
      (node (ref "C17") (pin "2") (pinfunction "2_2") (pintype "passive"))
      (node (ref "C26") (pin "2") (pinfunction "2_2") (pintype "passive"))
      (node (ref "C28") (pin "2") (pinfunction "2_2") (pintype "passive"))
      (node (ref "C29") (pin "2") (pinfunction "2_2") (pintype "passive"))
      (node (ref "C30") (pin "2") (pinfunction "2_2") (pintype "passive"))
      (node (ref "C34") (pin "2") (pinfunction "2_2") (pintype "passive"))
      (node (ref "C8") (pin "2") (pinfunction "2_2") (pintype "passive"))
      (node (ref "D5") (pin "1") (pinfunction "Cathode_1") (pintype "passive"))
      (node (ref "D6") (pin "1") (pinfunction "Cathode_1") (pintype "passive"))
      (node (ref "FB1") (pin "1") (pinfunction "1_1") (pintype "passive"))
      (node (ref "FB2") (pin "1") (pinfunction "1_1") (pintype "passive"))
      (node (ref "FB3") (pin "1") (pinfunction "1_1") (pintype "passive"))
      (node (ref "J1") (pin "2") (pinfunction "2_2") (pintype "passive"))
      (node (ref "J5") (pin "2") (pinfunction "2_2") (pintype "passive"))
      (node (ref "J6") (pin "2") (pinfunction "2_2") (pintype "passive"))
      (node (ref "JP4") (pin "2") (pinfunction "2_2") (pintype "passive"))
      (node (ref "R1") (pin "2") (pinfunction "2_2") (pintype "passive"))
      (node (ref "R14") (pin "2") (pinfunction "2_2") (pintype "passive"))
      (node (ref "R15") (pin "2") (pinfunction "2_2") (pintype "passive"))
      (node (ref "R17") (pin "2") (pinfunction "2_2") (pintype "passive"))
      (node (ref "R18") (pin "2") (pinfunction "2_2") (pintype "passive"))
      (node (ref "R19") (pin "2") (pinfunction "2_2") (pintype "passive"))
      (node (ref "R2") (pin "2") (pinfunction "2_2") (pintype "passive"))
      (node (ref "R20") (pin "2") (pinfunction "2_2") (pintype "passive"))
      (node (ref "R21") (pin "2") (pinfunction "2_2") (pintype "passive"))
      (node (ref "R27") (pin "2") (pinfunction "2_2") (pintype "passive"))
      (node (ref "R28") (pin "1") (pinfunction "1_1") (pintype "passive"))
      (node (ref "R3") (pin "2") (pinfunction "2_2") (pintype "passive"))
      (node (ref "R4") (pin "2") (pinfunction "2_2") (pintype "passive"))
      (node (ref "U4") (pin "5") (pinfunction "5_5") (pintype "passive"))
      (node (ref "U5") (pin "5") (pinfunction "5_5") (pintype "passive"))
      (node (ref "U6") (pin "5") (pinfunction "5_5") (pintype "passive"))
      (node (ref "U7") (pin "5") (pinfunction "5_5") (pintype "passive"))
    )
    (net (code "4") (name "+AREF") (class "Default")
      (node (ref "C21") (pin "2") (pinfunction "2_2") (pintype "passive"))
      (node (ref "C24") (pin "2") (pinfunction "2_2") (pintype "passive"))
      (node (ref "J4") (pin "8") (pinfunction "8_8") (pintype "passive"))
      (node (ref "U1") (pin "21") (pinfunction "AREF_21") (pintype "passive"))
    )
    (net (code "5") (name "/+3V3_16U2_UCAP") (class "Default")
      (node (ref "C7") (pin "2") (pinfunction "2_2") (pintype "passive"))
      (node (ref "R26") (pin "1") (pinfunction "1_1") (pintype "passive"))
      (node (ref "U2") (pin "27") (pinfunction "UCAP_27") (pintype "passive"))
    )
    (net (code "6") (name "/+5V_USB") (class "Default")
      (node (ref "C1") (pin "1") (pinfunction "1_1") (pintype "passive"))
      (node (ref "J7") (pin "1") (pinfunction "1_1") (pintype "passive"))
      (node (ref "L1") (pin "1") (pinfunction "1_1") (pintype "passive"))
    )
    (net (code "7") (name "/+5V{slash}3V3_16U2") (class "Default")
      (node (ref "C3") (pin "2") (pinfunction "2_2") (pintype "passive"))
      (node (ref "C4") (pin "2") (pinfunction "2_2") (pintype "passive"))
      (node (ref "C5") (pin "2") (pinfunction "2_2") (pintype "passive"))
      (node (ref "FB1") (pin "2") (pinfunction "2_2") (pintype "passive"))
      (node (ref "R26") (pin "2") (pinfunction "2_2") (pintype "passive"))
      (node (ref "U2") (pin "32") (pinfunction "AVCC_32") (pintype "passive"))
      (node (ref "U2") (pin "4") (pinfunction "VCC_4") (pintype "passive"))
    )
    (net (code "8") (name "/+5V{slash}3V3_328P_AVCC") (class "Default")
      (node (ref "C22") (pin "2") (pinfunction "2_2") (pintype "passive"))
      (node (ref "C23") (pin "2") (pinfunction "2_2") (pintype "passive"))
      (node (ref "FB3") (pin "2") (pinfunction "2_2") (pintype "passive"))
      (node (ref "U1") (pin "20") (pinfunction "AVCC_20") (pintype "passive"))
    )
    (net (code "9") (name "/+5V{slash}3V3_328P_VCC") (class "Default")
      (node (ref "C19") (pin "2") (pinfunction "2_2") (pintype "passive"))
      (node (ref "C20") (pin "2") (pinfunction "2_2") (pintype "passive"))
      (node (ref "FB2") (pin "2") (pinfunction "2_2") (pintype "passive"))
      (node (ref "U1") (pin "7") (pinfunction "VCC_7") (pintype "passive"))
    )
    (net (code "10") (name "/16U2PROG_328P_RESETn") (class "Default")
      (node (ref "JP1") (pin "2") (pinfunction "2_2") (pintype "passive"))
      (node (ref "R1") (pin "1") (pinfunction "1_1") (pintype "passive"))
      (node (ref "U2") (pin "13") (pinfunction "~{CTS}_/~{_HWB}_/__T0_/_AIN6_/_INT7_/_PD7_13") (pintype "passive"))
    )
    (net (code "11") (name "/16U2_16MHZ_XTAL1") (class "Default")
      (node (ref "C10") (pin "2") (pinfunction "2_2") (pintype "passive"))
      (node (ref "R9") (pin "1") (pinfunction "1_1") (pintype "passive"))
      (node (ref "U2") (pin "1") (pinfunction "XTAL1_1") (pintype "passive"))
      (node (ref "Y2") (pin "1") (pinfunction "1_1") (pintype "passive"))
    )
    (net (code "12") (name "/16U2_16MHZ_XTAL2") (class "Default")
      (node (ref "C9") (pin "2") (pinfunction "2_2") (pintype "passive"))
      (node (ref "R9") (pin "2") (pinfunction "2_2") (pintype "passive"))
      (node (ref "U2") (pin "2") (pinfunction "XTAL2_/_PC0_2") (pintype "passive"))
      (node (ref "Y2") (pin "2") (pinfunction "2_2") (pintype "passive"))
    )
    (net (code "13") (name "/16U2_BUF_RESETn") (class "Default")
      (node (ref "C31") (pin "2") (pinfunction "2_2") (pintype "passive"))
      (node (ref "R23") (pin "2") (pinfunction "2_2") (pintype "passive"))
      (node (ref "U5") (pin "1") (pinfunction "1_1") (pintype "passive"))
      (node (ref "U5") (pin "2") (pinfunction "2_2") (pintype "passive"))
    )
    (net (code "14") (name "/16U2_HDR_RESETn") (class "Default")
      (node (ref "J6") (pin "5") (pinfunction "5_5") (pintype "passive"))
      (node (ref "JP3") (pin "3") (pinfunction "3_3") (pintype "passive"))
    )
    (net (code "15") (name "/16U2_MISO") (class "Default")
      (node (ref "J6") (pin "1") (pinfunction "1_1") (pintype "passive"))
      (node (ref "U2") (pin "17") (pinfunction "PDO_/_MISO_/_PCINT3_/_PB3_17") (pintype "passive"))
    )
    (net (code "16") (name "/16U2_MOSI") (class "Default")
      (node (ref "J6") (pin "4") (pinfunction "4_4") (pintype "passive"))
      (node (ref "U2") (pin "16") (pinfunction "PDI_/_MOSI_/_PCINT2_/_PB2_16") (pintype "passive"))
    )
    (net (code "17") (name "/16U2_PB4") (class "Default")
      (node (ref "JP2") (pin "1") (pinfunction "1_1") (pintype "passive"))
      (node (ref "JP3") (pin "2") (pinfunction "2_2") (pintype "passive"))
      (node (ref "U2") (pin "18") (pinfunction "T1_/_PCINT4_/_PB4_18") (pintype "passive"))
    )
    (net (code "18") (name "/16U2_PB5") (class "Default")
      (node (ref "JP2") (pin "3") (pinfunction "3_3") (pintype "passive"))
      (node (ref "U2") (pin "19") (pinfunction "PCINT5_/_PB5_19") (pintype "passive"))
    )
    (net (code "19") (name "/16U2_PB6") (class "Default")
      (node (ref "JP2") (pin "2") (pinfunction "2_2") (pintype "passive"))
      (node (ref "U2") (pin "20") (pinfunction "PCINT6_/_PB6_20") (pintype "passive"))
    )
    (net (code "20") (name "/16U2_PB7") (class "Default")
      (node (ref "JP2") (pin "4") (pinfunction "4_4") (pintype "passive"))
      (node (ref "U2") (pin "21") (pinfunction "OC.0A_/_OC.1C_/_PCINT7_/_PB7_21") (pintype "passive"))
    )
    (net (code "21") (name "/16U2_RESETn") (class "Default")
      (node (ref "JP3") (pin "4") (pinfunction "4_4") (pintype "passive"))
      (node (ref "R4") (pin "1") (pinfunction "1_1") (pintype "passive"))
      (node (ref "U2") (pin "24") (pinfunction "PC1_/~{_RESET}_/_DW_24") (pintype "passive"))
      (node (ref "U5") (pin "4") (pinfunction "4_4") (pintype "passive"))
    )
    (net (code "22") (name "/16U2_RXD") (class "Default")
      (node (ref "R11") (pin "1") (pinfunction "1_1") (pintype "passive"))
      (node (ref "U2") (pin "8") (pinfunction "RXD1_/_AIN1_/_INT2_/_PD2_8") (pintype "passive"))
    )
    (net (code "23") (name "/16U2_RX_LED") (class "Default")
      (node (ref "D4") (pin "1") (pinfunction "Cathode_1") (pintype "passive"))
      (node (ref "U2") (pin "10") (pinfunction "AIN3_/_INT5_/_PD4_10") (pintype "passive"))
    )
    (net (code "24") (name "/16U2_SCLK") (class "Default")
      (node (ref "J6") (pin "3") (pinfunction "3_3") (pintype "passive"))
      (node (ref "R5") (pin "2") (pinfunction "2_2") (pintype "passive"))
    )
    (net (code "25") (name "/16U2_SCLK_R") (class "Default")
      (node (ref "R5") (pin "1") (pinfunction "1_1") (pintype "passive"))
      (node (ref "U2") (pin "15") (pinfunction "SCLK_/_PCINT1_/_PB1_15") (pintype "passive"))
    )
    (net (code "26") (name "/16U2_TXD") (class "Default")
      (node (ref "R10") (pin "1") (pinfunction "1_1") (pintype "passive"))
      (node (ref "U2") (pin "9") (pinfunction "TXD1_/_INT3_/_PD3_9") (pintype "passive"))
    )
    (net (code "27") (name "/16U2_TX_LED") (class "Default")
      (node (ref "D3") (pin "1") (pinfunction "Cathode_1") (pintype "passive"))
      (node (ref "U2") (pin "11") (pinfunction "XCK_/_AIN4_/_PCINT12_/_PD5_11") (pintype "passive"))
    )
    (net (code "28") (name "/328P_16MHZ_XTAL1") (class "Default")
      (node (ref "C27") (pin "2") (pinfunction "2_2") (pintype "passive"))
      (node (ref "R16") (pin "1") (pinfunction "1_1") (pintype "passive"))
      (node (ref "U1") (pin "9") (pinfunction "PB6_/_PCINT6_/_TOSC1_/_XTAL1_9") (pintype "passive"))
      (node (ref "Y1") (pin "1") (pinfunction "1_1") (pintype "passive"))
    )
    (net (code "29") (name "/328P_16MHZ_XTAL2") (class "Default")
      (node (ref "C25") (pin "2") (pinfunction "2_2") (pintype "passive"))
      (node (ref "R16") (pin "2") (pinfunction "2_2") (pintype "passive"))
      (node (ref "U1") (pin "10") (pinfunction "PB7_/_PCINT7_/_TOSC2_/_XTAL2_10") (pintype "passive"))
      (node (ref "Y1") (pin "2") (pinfunction "2_2") (pintype "passive"))
    )
    (net (code "30") (name "/328P_AUTORESETn") (class "Default")
      (node (ref "C11") (pin "1") (pinfunction "1_1") (pintype "passive"))
      (node (ref "R18") (pin "1") (pinfunction "1_1") (pintype "passive"))
      (node (ref "U6") (pin "1") (pinfunction "1_1") (pintype "passive"))
    )
    (net (code "31") (name "/328P_BUF_RESETn") (class "Default")
      (node (ref "C32") (pin "2") (pinfunction "2_2") (pintype "passive"))
      (node (ref "R24") (pin "2") (pinfunction "2_2") (pintype "passive"))
      (node (ref "U6") (pin "2") (pinfunction "2_2") (pintype "passive"))
    )
    (net (code "32") (name "/328P_RESETn") (class "Default")
      (node (ref "J1") (pin "3") (pinfunction "3_3") (pintype "passive"))
      (node (ref "J5") (pin "5") (pinfunction "5_5") (pintype "passive"))
      (node (ref "JP3") (pin "1") (pinfunction "1_1") (pintype "passive"))
      (node (ref "R14") (pin "1") (pinfunction "1_1") (pintype "passive"))
      (node (ref "U1") (pin "1") (pinfunction "PC6_/_PCINT14_/_~{_RESET}_1") (pintype "passive"))
      (node (ref "U6") (pin "4") (pinfunction "4_4") (pintype "passive"))
    )
    (net (code "33") (name "/AD0") (class "Default")
      (node (ref "J2") (pin "1") (pinfunction "1_1") (pintype "passive"))
      (node (ref "U1") (pin "23") (pinfunction "PCINT8_/_ADC0_/_PC0_23") (pintype "passive"))
    )
    (net (code "34") (name "/AD1") (class "Default")
      (node (ref "J2") (pin "2") (pinfunction "2_2") (pintype "passive"))
      (node (ref "U1") (pin "24") (pinfunction "PCINT9_/_ADC1_/_PC1_24") (pintype "passive"))
    )
    (net (code "35") (name "/AD2") (class "Default")
      (node (ref "J2") (pin "3") (pinfunction "3_3") (pintype "passive"))
      (node (ref "U1") (pin "25") (pinfunction "PCINT10_/_ADC2_/_PC2_25") (pintype "passive"))
    )
    (net (code "36") (name "/AD3") (class "Default")
      (node (ref "J2") (pin "4") (pinfunction "4_4") (pintype "passive"))
      (node (ref "U1") (pin "26") (pinfunction "PCINT11_/_ADC3_/_PC3_26") (pintype "passive"))
    )
    (net (code "37") (name "/AD4{slash}SDA") (class "Default")
      (node (ref "J2") (pin "5") (pinfunction "5_5") (pintype "passive"))
      (node (ref "J4") (pin "9") (pinfunction "9_9") (pintype "passive"))
      (node (ref "U1") (pin "27") (pinfunction "SDA_/_PCINT12_/_ADC4_/_PC4_27") (pintype "passive"))
    )
    (net (code "38") (name "/AD5{slash}SCL") (class "Default")
      (node (ref "J2") (pin "6") (pinfunction "6_6") (pintype "passive"))
      (node (ref "J4") (pin "10") (pinfunction "10_10") (pintype "passive"))
      (node (ref "U1") (pin "28") (pinfunction "SCL_/_PCINT13_/_ADC5_/_PC5_28") (pintype "passive"))
    )
    (net (code "39") (name "/BUTTON_RESETn") (class "Default")
      (node (ref "D6") (pin "2") (pinfunction "Anode_2") (pintype "passive"))
      (node (ref "R20") (pin "1") (pinfunction "1_1") (pintype "passive"))
      (node (ref "R24") (pin "1") (pinfunction "1_1") (pintype "passive"))
      (node (ref "SW1") (pin "1") (pinfunction "1_1") (pintype "passive"))
      (node (ref "SW1") (pin "2") (pinfunction "2_2") (pintype "passive"))
    )
    (net (code "40") (name "/CON_USB_N") (class "Default")
      (node (ref "J7") (pin "2") (pinfunction "2_2") (pintype "passive"))
      (node (ref "R6") (pin "1") (pinfunction "1_1") (pintype "passive"))
      (node (ref "Z1") (pin "2") (pinfunction "2_2") (pintype "passive"))
    )
    (net (code "41") (name "/CON_USB_P") (class "Default")
      (node (ref "J7") (pin "3") (pinfunction "3_3") (pintype "passive"))
      (node (ref "R7") (pin "1") (pinfunction "1_1") (pintype "passive"))
      (node (ref "Z2") (pin "2") (pinfunction "2_2") (pintype "passive"))
    )
    (net (code "42") (name "/IO0") (class "Default")
      (node (ref "J3") (pin "1") (pinfunction "1_1") (pintype "passive"))
      (node (ref "R10") (pin "2") (pinfunction "2_2") (pintype "passive"))
      (node (ref "U1") (pin "2") (pinfunction "RXD_/_PCINT16_/_PD0_2") (pintype "passive"))
    )
    (net (code "43") (name "/IO1") (class "Default")
      (node (ref "J3") (pin "2") (pinfunction "2_2") (pintype "passive"))
      (node (ref "R11") (pin "2") (pinfunction "2_2") (pintype "passive"))
      (node (ref "U1") (pin "3") (pinfunction "TXD_/_PCINT17_/_PD1_3") (pintype "passive"))
    )
    (net (code "44") (name "/IO2") (class "Default")
      (node (ref "J3") (pin "3") (pinfunction "3_3") (pintype "passive"))
      (node (ref "U1") (pin "4") (pinfunction "INT0_/_PCINT18_/_PD2_4") (pintype "passive"))
    )
    (net (code "45") (name "/IO3") (class "Default")
      (node (ref "J3") (pin "4") (pinfunction "4_4") (pintype "passive"))
      (node (ref "U1") (pin "5") (pinfunction "OC2B_/_INT1_/_PCINT19_/_PD3_5") (pintype "passive"))
    )
    (net (code "46") (name "/IO4") (class "Default")
      (node (ref "J3") (pin "5") (pinfunction "5_5") (pintype "passive"))
      (node (ref "U1") (pin "6") (pinfunction "XCK_/_T0_/_PCINT20_/_PD4_6") (pintype "passive"))
    )
    (net (code "47") (name "/IO5") (class "Default")
      (node (ref "J3") (pin "6") (pinfunction "6_6") (pintype "passive"))
      (node (ref "U1") (pin "11") (pinfunction "OC0B_/_T1_/_PCINT21_/_PD5_11") (pintype "passive"))
    )
    (net (code "48") (name "/IO6") (class "Default")
      (node (ref "J3") (pin "7") (pinfunction "7_7") (pintype "passive"))
      (node (ref "U1") (pin "12") (pinfunction "OC0A_/_AIN0_/_PCINT22_/_PD6_12") (pintype "passive"))
    )
    (net (code "49") (name "/IO7") (class "Default")
      (node (ref "J3") (pin "8") (pinfunction "8_8") (pintype "passive"))
      (node (ref "U1") (pin "13") (pinfunction "AIN1_/_PCINT23_/_PD7_13") (pintype "passive"))
    )
    (net (code "50") (name "/IO8") (class "Default")
      (node (ref "J4") (pin "1") (pinfunction "1_1") (pintype "passive"))
      (node (ref "R22") (pin "2") (pinfunction "2_2") (pintype "passive"))
      (node (ref "U1") (pin "14") (pinfunction "CLKO_/_ICP1_/_PCINT0_/_PB0_14") (pintype "passive"))
    )
    (net (code "51") (name "/IO9") (class "Default")
      (node (ref "J4") (pin "2") (pinfunction "2_2") (pintype "passive"))
      (node (ref "U1") (pin "15") (pinfunction "OC1A_/_PCINT1_/_PB1_15") (pintype "passive"))
    )
    (net (code "52") (name "/MISO") (class "Default")
      (node (ref "J4") (pin "5") (pinfunction "5_5") (pintype "passive"))
      (node (ref "J5") (pin "1") (pinfunction "1_1") (pintype "passive"))
      (node (ref "U1") (pin "18") (pinfunction "MISO_/_PCINT4_/_PB4_18") (pintype "passive"))
    )
    (net (code "53") (name "/MOSI") (class "Default")
      (node (ref "J4") (pin "4") (pinfunction "4_4") (pintype "passive"))
      (node (ref "J5") (pin "4") (pinfunction "4_4") (pintype "passive"))
      (node (ref "U1") (pin "17") (pinfunction "MOSI_/_OC2A_/_PCINT3_/_PB3_17") (pintype "passive"))
    )
    (net (code "54") (name "/SCK") (class "Default")
      (node (ref "J4") (pin "6") (pinfunction "6_6") (pintype "passive"))
      (node (ref "J5") (pin "3") (pinfunction "3_3") (pintype "passive"))
      (node (ref "R13") (pin "2") (pinfunction "2_2") (pintype "passive"))
      (node (ref "U4") (pin "1") (pinfunction "1_1") (pintype "passive"))
      (node (ref "U4") (pin "2") (pinfunction "2_2") (pintype "passive"))
    )
    (net (code "55") (name "/SCK_R") (class "Default")
      (node (ref "R13") (pin "1") (pinfunction "1_1") (pintype "passive"))
      (node (ref "U1") (pin "19") (pinfunction "SCK_/_PCINT5_/_PB5_19") (pintype "passive"))
    )
    (net (code "56") (name "/SS") (class "Default")
      (node (ref "J4") (pin "3") (pinfunction "3_3") (pintype "passive"))
      (node (ref "U1") (pin "16") (pinfunction "~{SS}_/_OC1B_/_PCINT2_/_PB2_16") (pintype "passive"))
    )
    (net (code "57") (name "/USB_N") (class "Default")
      (node (ref "R6") (pin "2") (pinfunction "2_2") (pintype "passive"))
      (node (ref "U2") (pin "30") (pinfunction "D-_30") (pintype "passive"))
    )
    (net (code "58") (name "/USB_P") (class "Default")
      (node (ref "R7") (pin "2") (pinfunction "2_2") (pintype "passive"))
      (node (ref "U2") (pin "29") (pinfunction "D+_29") (pintype "passive"))
    )
    (net (code "59") (name "/USER_BUTTON") (class "Default")
      (node (ref "R21") (pin "1") (pinfunction "1_1") (pintype "passive"))
      (node (ref "R25") (pin "1") (pinfunction "1_1") (pintype "passive"))
      (node (ref "SW2") (pin "1") (pinfunction "1_1") (pintype "passive"))
      (node (ref "SW2") (pin "2") (pinfunction "2_2") (pintype "passive"))
    )
    (net (code "60") (name "/USER_BUTTON_BUF") (class "Default")
      (node (ref "C33") (pin "2") (pinfunction "2_2") (pintype "passive"))
      (node (ref "R25") (pin "2") (pinfunction "2_2") (pintype "passive"))
      (node (ref "U7") (pin "1") (pinfunction "1_1") (pintype "passive"))
      (node (ref "U7") (pin "2") (pinfunction "2_2") (pintype "passive"))
    )
    (net (code "61") (name "GND") (class "Default")
      (node (ref "C1") (pin "2") (pinfunction "2_2") (pintype "passive"))
      (node (ref "C10") (pin "1") (pinfunction "1_1") (pintype "passive"))
      (node (ref "C12") (pin "1") (pinfunction "1_1") (pintype "passive"))
      (node (ref "C13") (pin "1") (pinfunction "1_1") (pintype "passive"))
      (node (ref "C14") (pin "1") (pinfunction "1_1") (pintype "passive"))
      (node (ref "C15") (pin "1") (pinfunction "1_1") (pintype "passive"))
      (node (ref "C16") (pin "1") (pinfunction "1_1") (pintype "passive"))
      (node (ref "C17") (pin "1") (pinfunction "1_1") (pintype "passive"))
      (node (ref "C19") (pin "1") (pinfunction "1_1") (pintype "passive"))
      (node (ref "C2") (pin "2") (pinfunction "2_2") (pintype "passive"))
      (node (ref "C20") (pin "1") (pinfunction "1_1") (pintype "passive"))
      (node (ref "C21") (pin "1") (pinfunction "1_1") (pintype "passive"))
      (node (ref "C22") (pin "1") (pinfunction "1_1") (pintype "passive"))
      (node (ref "C23") (pin "1") (pinfunction "1_1") (pintype "passive"))
      (node (ref "C24") (pin "1") (pinfunction "1_1") (pintype "passive"))
      (node (ref "C25") (pin "1") (pinfunction "1_1") (pintype "passive"))
      (node (ref "C26") (pin "1") (pinfunction "1_1") (pintype "passive"))
      (node (ref "C27") (pin "1") (pinfunction "1_1") (pintype "passive"))
      (node (ref "C28") (pin "1") (pinfunction "1_1") (pintype "passive"))
      (node (ref "C29") (pin "1") (pinfunction "1_1") (pintype "passive"))
      (node (ref "C3") (pin "1") (pinfunction "1_1") (pintype "passive"))
      (node (ref "C30") (pin "1") (pinfunction "1_1") (pintype "passive"))
      (node (ref "C31") (pin "1") (pinfunction "1_1") (pintype "passive"))
      (node (ref "C32") (pin "1") (pinfunction "1_1") (pintype "passive"))
      (node (ref "C33") (pin "1") (pinfunction "1_1") (pintype "passive"))
      (node (ref "C34") (pin "1") (pinfunction "1_1") (pintype "passive"))
      (node (ref "C4") (pin "1") (pinfunction "1_1") (pintype "passive"))
      (node (ref "C5") (pin "1") (pinfunction "1_1") (pintype "passive"))
      (node (ref "C6") (pin "1") (pinfunction "1_1") (pintype "passive"))
      (node (ref "C7") (pin "1") (pinfunction "1_1") (pintype "passive"))
      (node (ref "C8") (pin "1") (pinfunction "1_1") (pintype "passive"))
      (node (ref "C9") (pin "1") (pinfunction "1_1") (pintype "passive"))
      (node (ref "D1") (pin "1") (pinfunction "Cathode_1") (pintype "passive"))
      (node (ref "J1") (pin "6") (pinfunction "6_6") (pintype "passive"))
      (node (ref "J1") (pin "7") (pinfunction "7_7") (pintype "passive"))
      (node (ref "J4") (pin "7") (pinfunction "7_7") (pintype "passive"))
      (node (ref "J5") (pin "6") (pinfunction "6_6") (pintype "passive"))
      (node (ref "J6") (pin "6") (pinfunction "6_6") (pintype "passive"))
      (node (ref "J7") (pin "10") (pinfunction "10_10") (pintype "passive"))
      (node (ref "J7") (pin "11") (pinfunction "11_11") (pintype "passive"))
      (node (ref "J7") (pin "5") (pinfunction "5_5") (pintype "passive"))
      (node (ref "J7") (pin "6") (pinfunction "6_6") (pintype "passive"))
      (node (ref "J7") (pin "7") (pinfunction "7_7") (pintype "passive"))
      (node (ref "J7") (pin "8") (pinfunction "8_8") (pintype "passive"))
      (node (ref "J7") (pin "9") (pinfunction "9_9") (pintype "passive"))
      (node (ref "J9") (pin "1") (pinfunction "1_1") (pintype "passive"))
      (node (ref "MH1") (pin "1") (pinfunction "1_1") (pintype "passive"))
      (node (ref "MH2") (pin "1") (pinfunction "1_1") (pintype "passive"))
      (node (ref "MH3") (pin "1") (pinfunction "1_1") (pintype "passive"))
      (node (ref "R12") (pin "1") (pinfunction "1_1") (pintype "passive"))
      (node (ref "R8") (pin "2") (pinfunction "2_2") (pintype "passive"))
      (node (ref "SW1") (pin "3") (pinfunction "3_3") (pintype "passive"))
      (node (ref "SW1") (pin "4") (pinfunction "4_4") (pintype "passive"))
      (node (ref "SW2") (pin "3") (pinfunction "3_3") (pintype "passive"))
      (node (ref "SW2") (pin "4") (pinfunction "4_4") (pintype "passive"))
      (node (ref "U1") (pin "22") (pinfunction "GND_2_22") (pintype "passive"))
      (node (ref "U1") (pin "8") (pinfunction "GND_1_8") (pintype "passive"))
      (node (ref "U2") (pin "28") (pinfunction "UGND_28") (pintype "passive"))
      (node (ref "U2") (pin "3") (pinfunction "GND_3") (pintype "passive"))
      (node (ref "U3") (pin "3") (pinfunction "GND_3") (pintype "passive"))
      (node (ref "U3") (pin "6") (pinfunction "EPAD_6") (pintype "passive"))
      (node (ref "U4") (pin "3") (pinfunction "3_3") (pintype "passive"))
      (node (ref "U5") (pin "3") (pinfunction "3_3") (pintype "passive"))
      (node (ref "U6") (pin "3") (pinfunction "3_3") (pintype "passive"))
      (node (ref "U7") (pin "3") (pinfunction "3_3") (pintype "passive"))
      (node (ref "Z1") (pin "1") (pinfunction "1_1") (pintype "passive"))
      (node (ref "Z2") (pin "1") (pinfunction "1_1") (pintype "passive"))
    )
    (net (code "62") (name "Net-(C11-Pad2)") (class "Default")
      (node (ref "C11") (pin "2") (pinfunction "2_2") (pintype "passive"))
      (node (ref "JP1") (pin "1") (pinfunction "1_1") (pintype "passive"))
    )
    (net (code "63") (name "Net-(D1-Anode)") (class "Default")
      (node (ref "D1") (pin "2") (pinfunction "Anode_2") (pintype "passive"))
      (node (ref "R17") (pin "1") (pinfunction "1_1") (pintype "passive"))
    )
    (net (code "64") (name "Net-(D2-Anode)") (class "Default")
      (node (ref "D2") (pin "2") (pinfunction "Anode_2") (pintype "passive"))
      (node (ref "R15") (pin "1") (pinfunction "1_1") (pintype "passive"))
    )
    (net (code "65") (name "Net-(D2-Cathode)") (class "Default")
      (node (ref "D2") (pin "1") (pinfunction "Cathode_1") (pintype "passive"))
      (node (ref "U4") (pin "4") (pinfunction "4_4") (pintype "passive"))
    )
    (net (code "66") (name "Net-(D3-Anode)") (class "Default")
      (node (ref "D3") (pin "2") (pinfunction "Anode_2") (pintype "passive"))
      (node (ref "R2") (pin "1") (pinfunction "1_1") (pintype "passive"))
    )
    (net (code "67") (name "Net-(D4-Anode)") (class "Default")
      (node (ref "D4") (pin "2") (pinfunction "Anode_2") (pintype "passive"))
      (node (ref "R3") (pin "1") (pinfunction "1_1") (pintype "passive"))
    )
    (net (code "68") (name "Net-(D5-Anode)") (class "Default")
      (node (ref "D5") (pin "2") (pinfunction "Anode_2") (pintype "passive"))
      (node (ref "R19") (pin "1") (pinfunction "1_1") (pintype "passive"))
      (node (ref "R23") (pin "1") (pinfunction "1_1") (pintype "passive"))
    )
    (net (code "69") (name "Net-(J7-Pad4)") (class "Default")
      (node (ref "J7") (pin "4") (pinfunction "4_4") (pintype "passive"))
      (node (ref "R8") (pin "1") (pinfunction "1_1") (pintype "passive"))
    )
    (net (code "70") (name "Net-(JP1-Pad3)") (class "Default")
      (node (ref "JP1") (pin "3") (pinfunction "3_3") (pintype "passive"))
      (node (ref "R12") (pin "2") (pinfunction "2_2") (pintype "passive"))
    )
    (net (code "71") (name "Net-(R22-Pad1)") (class "Default")
      (node (ref "R22") (pin "1") (pinfunction "1_1") (pintype "passive"))
      (node (ref "U7") (pin "4") (pinfunction "4_4") (pintype "passive"))
    )
    (net (code "72") (name "unconnected-(J1-Pad1)") (class "Default")
      (node (ref "J1") (pin "1") (pinfunction "1_1") (pintype "passive+no_connect"))
    )
    (net (code "73") (name "unconnected-(J1-Pad8)") (class "Default")
      (node (ref "J1") (pin "8") (pinfunction "8_8") (pintype "passive+no_connect"))
    )
    (net (code "74") (name "unconnected-(MH4-Pad1)") (class "Default")
      (node (ref "MH4") (pin "1") (pinfunction "1_1") (pintype "passive+no_connect"))
    )
    (net (code "75") (name "unconnected-(U2-AIN0_{slash}_INT1_{slash}_PD1-Pad7)") (class "Default")
      (node (ref "U2") (pin "7") (pinfunction "AIN0_/_INT1_/_PD1_7") (pintype "passive+no_connect"))
    )
    (net (code "76") (name "unconnected-(U2-AIN2_{slash}_PCINT11_{slash}_PC2-Pad5)") (class "Default")
      (node (ref "U2") (pin "5") (pinfunction "AIN2_/_PCINT11_/_PC2_5") (pintype "passive+no_connect"))
    )
    (net (code "77") (name "unconnected-(U2-CLKO_{slash}_ICP1_{slash}_INT4_{slash}_PC7-Pad22)") (class "Default")
      (node (ref "U2") (pin "22") (pinfunction "CLKO_/_ICP1_/_INT4_/_PC7_22") (pintype "passive+no_connect"))
    )
    (net (code "78") (name "unconnected-(U2-OC.0B_{slash}_INT0_{slash}_PD0-Pad6)") (class "Default")
      (node (ref "U2") (pin "6") (pinfunction "OC.0B_/_INT0_/_PD0_6") (pintype "passive+no_connect"))
    )
    (net (code "79") (name "unconnected-(U2-OC.1A_{slash}_PCINT8_{slash}_PC6-Pad23)") (class "Default")
      (node (ref "U2") (pin "23") (pinfunction "OC.1A_/_PCINT8_/_PC6_23") (pintype "passive+no_connect"))
    )
    (net (code "80") (name "unconnected-(U2-OC.1B_{slash}_PCINT9_{slash}_PC5-Pad25)") (class "Default")
      (node (ref "U2") (pin "25") (pinfunction "OC.1B_/_PCINT9_/_PC5_25") (pintype "passive+no_connect"))
    )
    (net (code "81") (name "unconnected-(U2-PCINT10_{slash}_PC4-Pad26)") (class "Default")
      (node (ref "U2") (pin "26") (pinfunction "PCINT10_/_PC4_26") (pintype "passive+no_connect"))
    )
    (net (code "82") (name "unconnected-(U2-~{RTS}_{slash}_AIN5_{slash}_INT6_{slash}_PD6-Pad12)") (class "Default")
      (node (ref "U2") (pin "12") (pinfunction "~{RTS}_/_AIN5_/_INT6_/_PD6_12") (pintype "passive+no_connect"))
    )
    (net (code "83") (name "unconnected-(U2-~{SS}_{slash}_PCINT0_{slash}_PB0-Pad14)") (class "Default")
      (node (ref "U2") (pin "14") (pinfunction "~{SS}_/_PCINT0_/_PB0_14") (pintype "passive+no_connect"))
    )
  )
)
